# Control_Sense_TOPMOS.net
KiCad netlist of a schematic drawn in Altium Designer
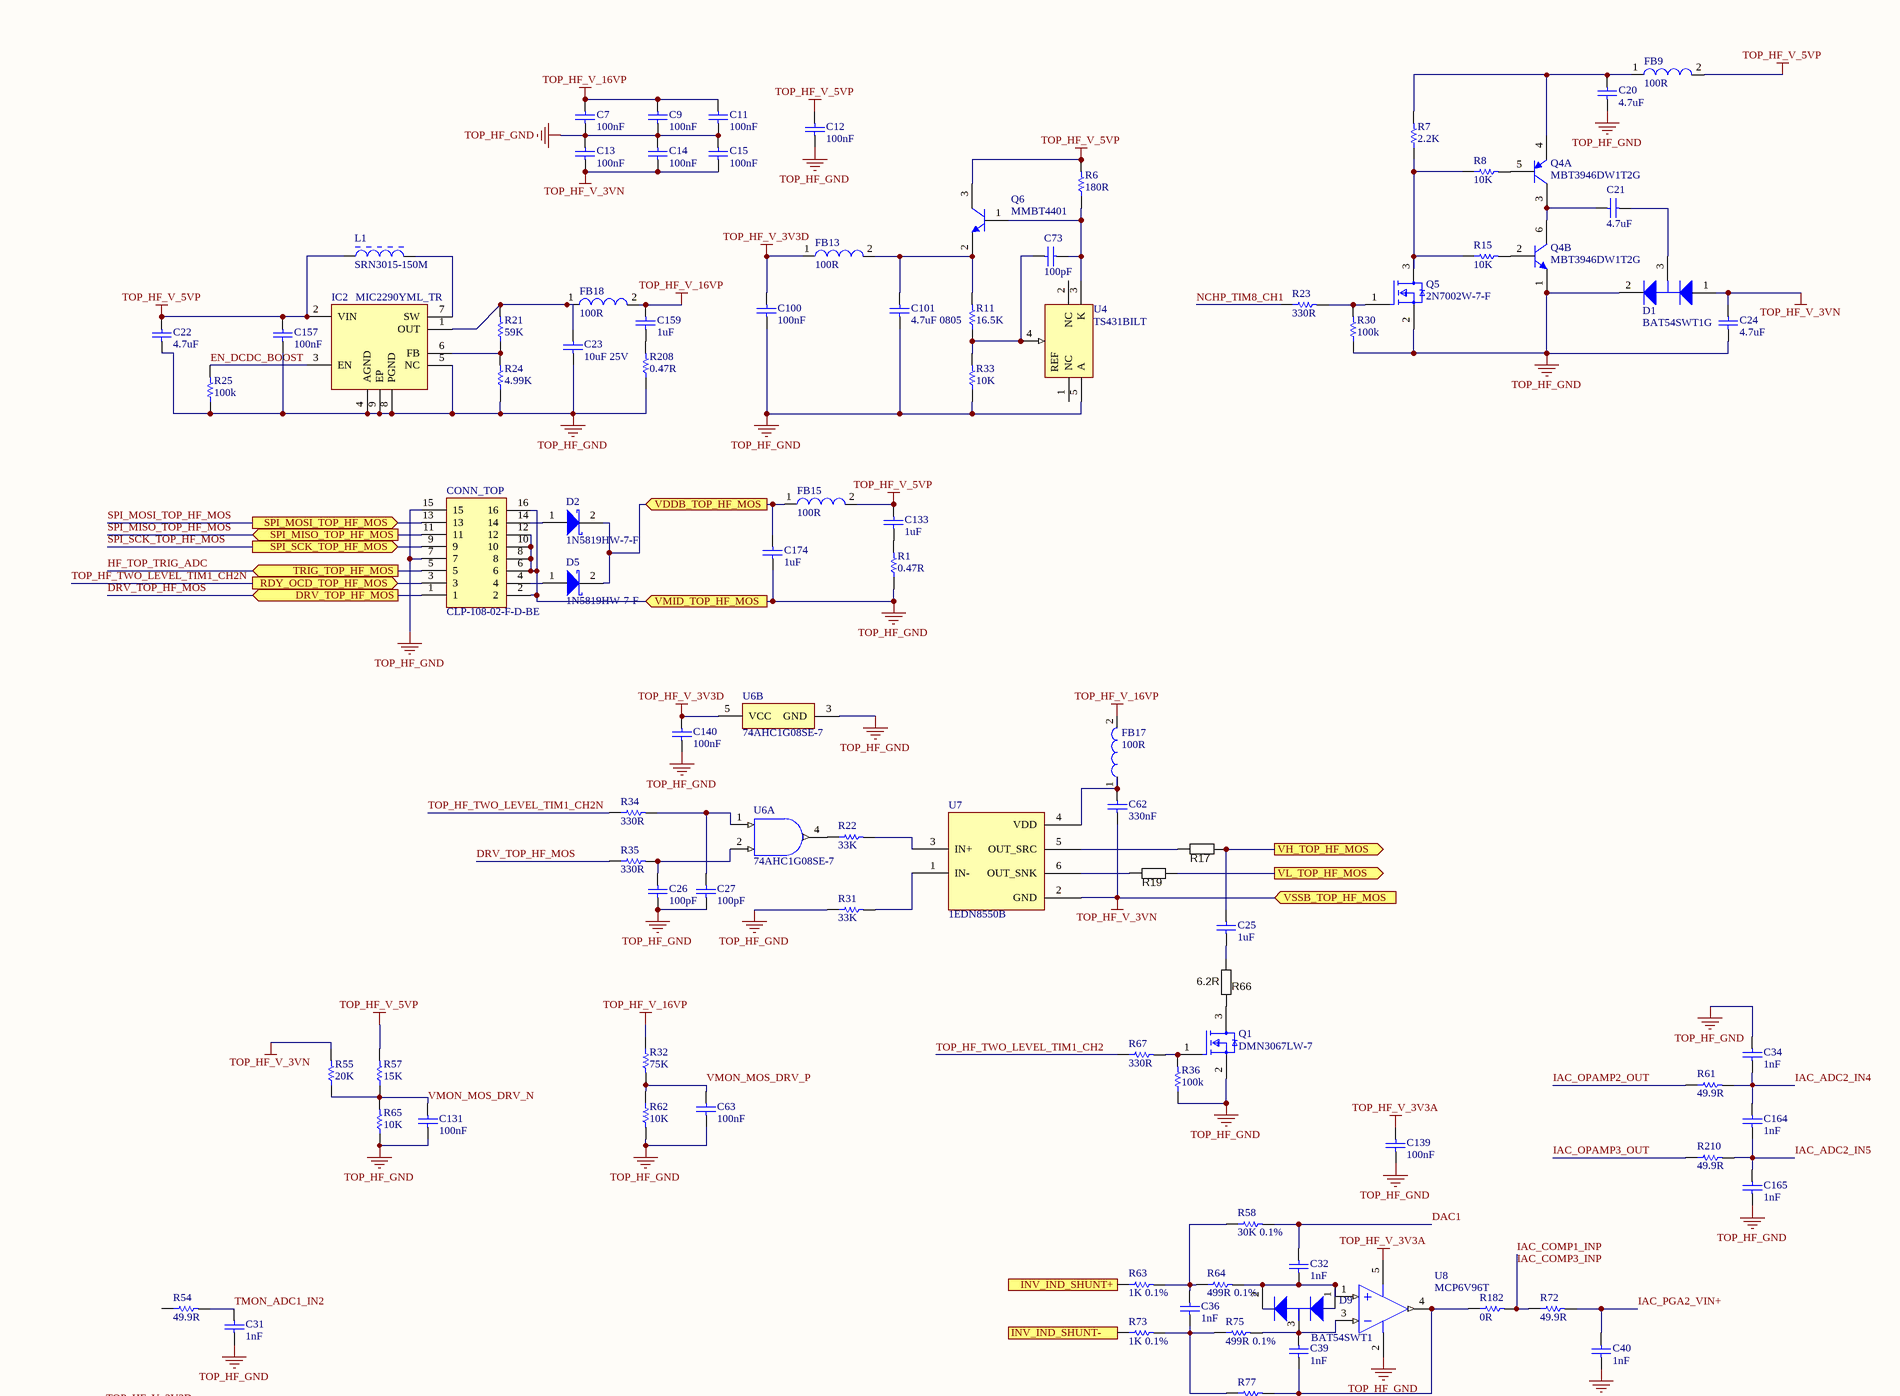
[diagram p0: Control_Sense_TOPMOS.SchDoc, top]
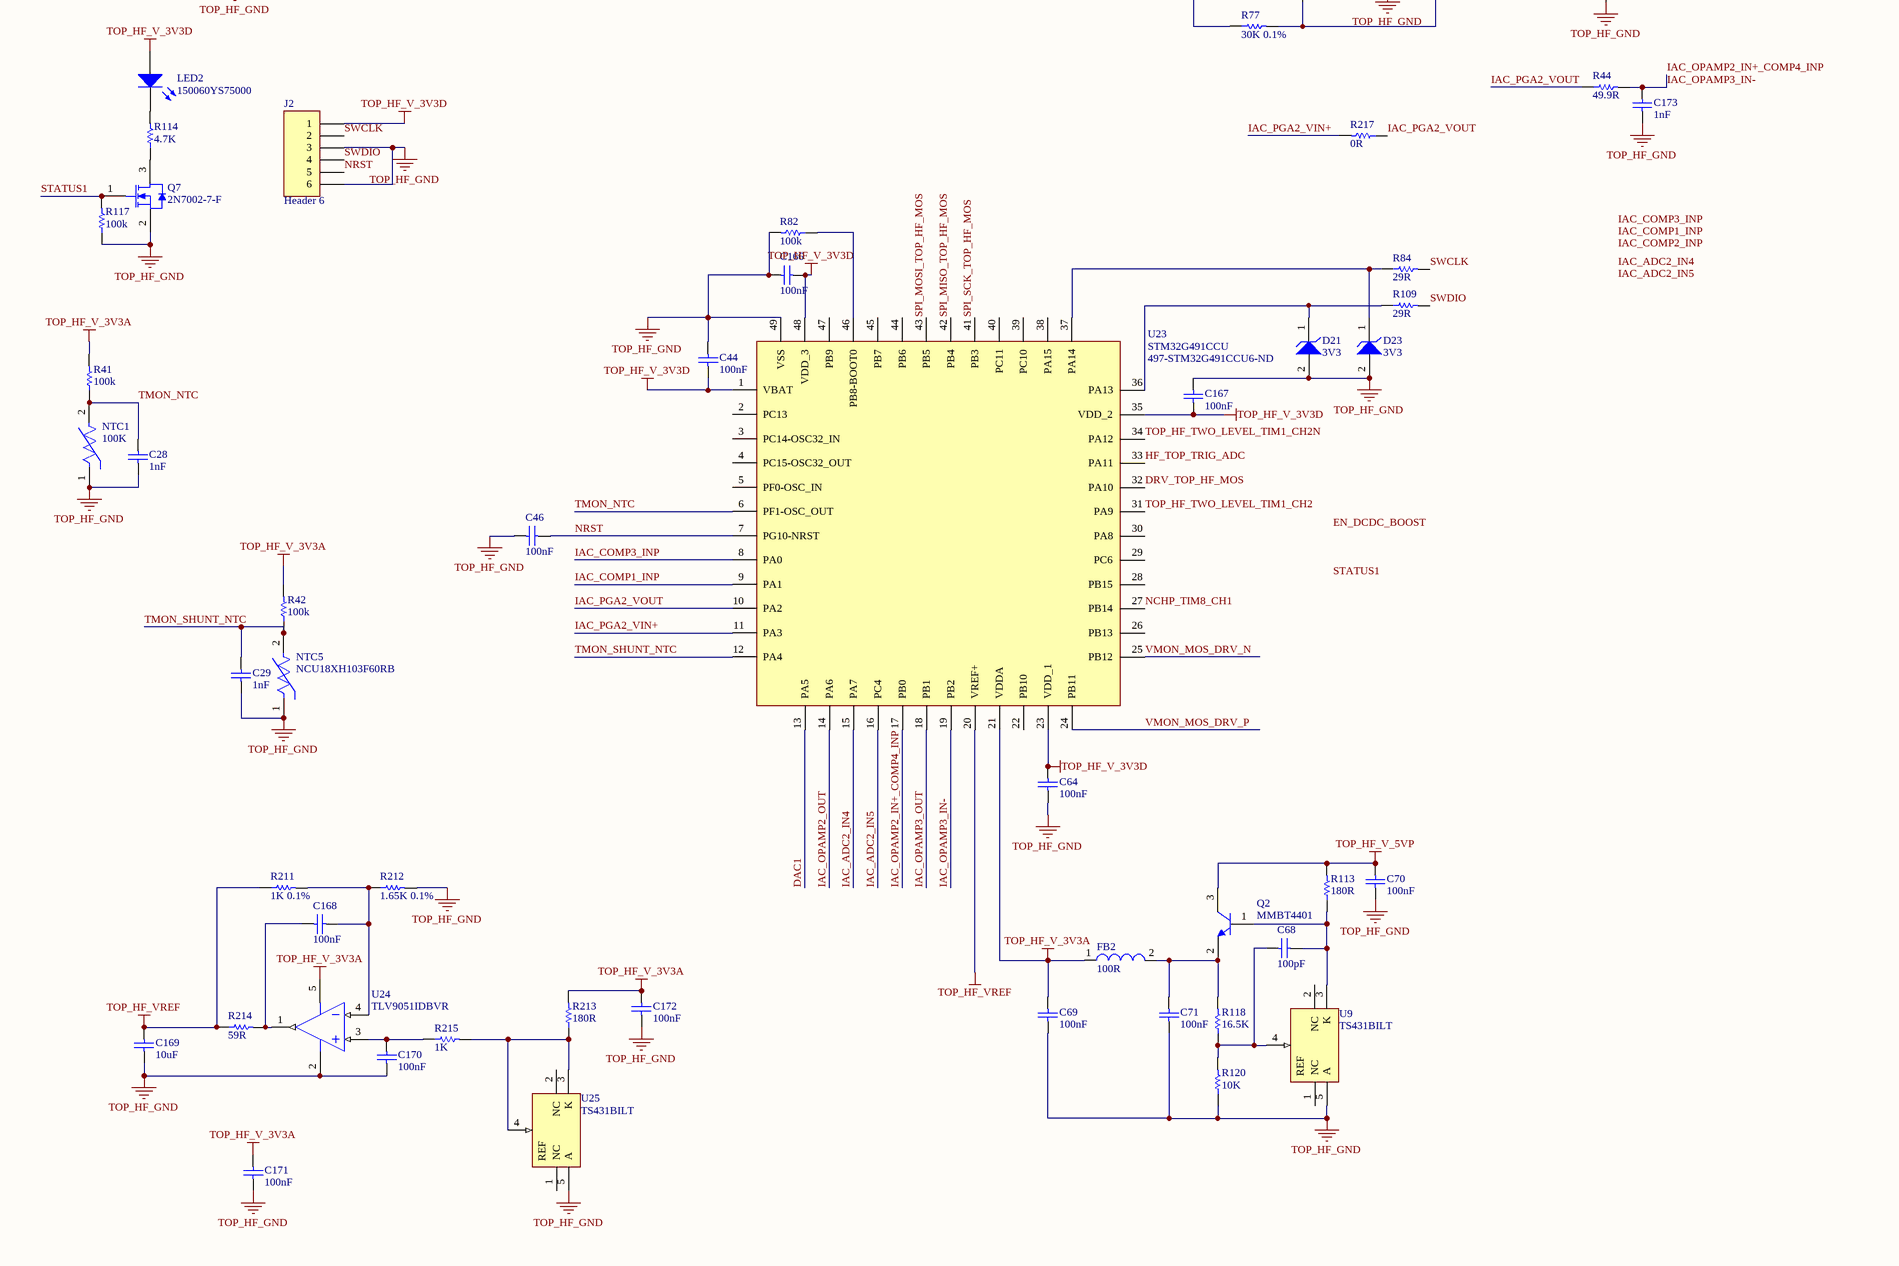
[diagram p1: Control_Sense_TOPMOS.SchDoc, bottom]

(export (version "E")
  (design (tool "Eeschema 10.0.6"))
  (components
    (comp (ref "C7")
      (value "100nF")
      (footprint "CAPC1608X90X35ML15T15")
      (fields
        (field (name "MANUFACTURER") "AVX Interconnect / Elco")
        (field (name "PART NUMBER") "06035A151JAT2A.")
        (field (name "MANUFACTURER PART NUMBER") "06035A151JAT2A")
      )
      (libsource (lib "Altium Content Vault") (part "CAP"))
    )
    (comp (ref "C9")
      (value "100nF")
      (footprint "CAPC1608X90X35ML15T15")
      (fields
        (field (name "MANUFACTURER") "AVX Interconnect / Elco")
        (field (name "PART NUMBER") "06035A151JAT2A.")
        (field (name "MANUFACTURER PART NUMBER") "06035A151JAT2A")
      )
      (libsource (lib "Altium Content Vault") (part "CAP"))
    )
    (comp (ref "C11")
      (value "100nF")
      (footprint "CAPC1608X90X35NL15T15")
      (fields
        (field (name "MANUFACTURER") "AVX Interconnect / Elco")
        (field (name "PART NUMBER") "06035A151JAT2A.")
        (field (name "MANUFACTURER PART NUMBER") "06035A151JAT2A")
      )
      (libsource (lib "Altium Content Vault") (part "CAP"))
    )
    (comp (ref "C12")
      (value "100nF")
      (footprint "CAPC1608X90X35NL15T15")
      (fields
        (field (name "MANUFACTURER") "AVX Interconnect / Elco")
        (field (name "PART NUMBER") "06035A151JAT2A.")
        (field (name "MANUFACTURER PART NUMBER") "06035A151JAT2A")
      )
      (libsource (lib "Altium Content Vault") (part "CAP"))
    )
    (comp (ref "C13")
      (value "100nF")
      (footprint "CAPC1608X90X35ML15T15")
      (fields
        (field (name "MANUFACTURER") "AVX Interconnect / Elco")
        (field (name "PART NUMBER") "06035A151JAT2A.")
        (field (name "MANUFACTURER PART NUMBER") "06035A151JAT2A")
      )
      (libsource (lib "Altium Content Vault") (part "CAP"))
    )
    (comp (ref "C14")
      (value "100nF")
      (footprint "CAPC1608X90X35ML15T15")
      (fields
        (field (name "MANUFACTURER") "AVX Interconnect / Elco")
        (field (name "PART NUMBER") "06035A151JAT2A.")
        (field (name "MANUFACTURER PART NUMBER") "06035A151JAT2A")
      )
      (libsource (lib "Altium Content Vault") (part "CAP"))
    )
    (comp (ref "C15")
      (value "100nF")
      (footprint "CAPC1608X90X35NL15T15")
      (fields
        (field (name "MANUFACTURER") "AVX Interconnect / Elco")
        (field (name "PART NUMBER") "06035A151JAT2A.")
        (field (name "MANUFACTURER PART NUMBER") "06035A151JAT2A")
      )
      (libsource (lib "Altium Content Vault") (part "CAP"))
    )
    (comp (ref "C20")
      (value "4.7uF")
      (footprint "SAMS-C0603-2_L")
      (description "Cap Ceramic 0.1uF 50VDC X7R 10% SMD 0603 Paper T/R")
      (fields
        (field (name "MANUFACTURER") "Samsung Electro-Mechanics")
        (field (name "MANUFACTURER PART NUMBER") "CL10B104KB8NNNC")
      )
      (libsource (lib "Altium Content Vault") (part "CAP-NP-2"))
    )
    (comp (ref "C21")
      (value "4.7uF")
      (footprint "SAMS-C0603-2_L")
      (description "Cap Ceramic 0.1uF 50VDC X7R 10% SMD 0603 Paper T/R")
      (fields
        (field (name "MANUFACTURER") "Samsung Electro-Mechanics")
        (field (name "MANUFACTURER PART NUMBER") "CL10B104KB8NNNC")
      )
      (libsource (lib "Altium Content Vault") (part "CAP-NP-2"))
    )
    (comp (ref "C22")
      (value "4.7uF")
      (footprint "CAPC2013X145X20NL20")
      (description "Chip Capacitor, 4.7 uF, +/- 10%, 25 V, -55 to 125 degC, 0805 (2012 Metric), RoHS, Tape and Reel")
      (fields (field (name "MANUFACTURER") "TDK") (field (name "TOLERANCE") "±10%"))
      (libsource (lib "Altium Content Vault") (part "CAP-NP-2"))
    )
    (comp (ref "C23")
      (value "10uF 25V")
      (footprint "CAPC3216X229X50LL20T25")
      (description "Chip Capacitor, 10 uF, +/- 10%, 25 V, -55 to 85 degC, 1206 (3216 Metric), RoHS, Tape and Reel")
      (fields (field (name "MANUFACTURER") "AVX"))
      (libsource (lib "Altium Content Vault") (part "CAP-NP-2"))
    )
    (comp (ref "C24")
      (value "4.7uF")
      (footprint "SAMS-C0603-2_L")
      (description "Cap Ceramic 4.7uF 6.3VDC X5R 10% SMD 0603 Paper T/R")
      (fields
        (field (name "MANUFACTURER") "Samsung Electro-Mechanics")
        (field (name "MANUFACTURER PART NUMBER") "CL10B104KB8NNNC")
      )
      (libsource (lib "Altium Content Vault") (part "CAP-NP-2"))
    )
    (comp (ref "C25")
      (value "1uF")
      (footprint "CAPC2013X135X45ML10T25")
      (description "Chip Capacitor, 0.1 uF, +/- 10%, 50 V, -55 to 125 degC, 0805 (2012 Metric), RoHS, Tape and Reel")
      (fields (field (name "VOLTAGE") "50V") (field (name "TOLERANCE") "10%"))
      (libsource (lib "Altium Content Vault") (part "CAP-NP-2"))
    )
    (comp (ref "C26")
      (value "100pF")
      (footprint "CAPC1608X90X35NL10T15")
      (fields
        (field (name "PART NUMBER") "GRM1885C1H101JA01D")
        (field (name "MANUFACTURER") "Murata")
        (field (name "TOLERANCE") "5%")
      )
      (libsource (lib "Altium Content Vault") (part "CAP"))
    )
    (comp (ref "C27")
      (value "100pF")
      (footprint "CAPC1608X90X35NL10T15")
      (fields
        (field (name "PART NUMBER") "GRM1885C1H101JA01D")
        (field (name "MANUFACTURER") "Murata")
        (field (name "TOLERANCE") "5%")
      )
      (libsource (lib "Altium Content Vault") (part "CAP"))
    )
    (comp (ref "C28")
      (value "1nF")
      (footprint "CAPC1005X56X25NL10T15")
      (fields
        (field (name "MANUFACTURER") "AVX Interconnect / Elco")
        (field (name "PART NUMBER") "04025C102MAT2A")
        (field (name "TOLERANCE") "20%")
      )
      (libsource (lib "Altium Content Vault") (part "CAP"))
    )
    (comp (ref "C29")
      (value "1nF")
      (footprint "CAPC1005X56X25NL10T15")
      (fields
        (field (name "MANUFACTURER") "AVX Interconnect / Elco")
        (field (name "PART NUMBER") "04025C102MAT2A")
        (field (name "TOLERANCE") "20%")
      )
      (libsource (lib "Altium Content Vault") (part "CAP"))
    )
    (comp (ref "C31")
      (value "1nF")
      (footprint "CAPC1005X56X25LL10T15")
      (fields
        (field (name "MANUFACTURER") "AVX Interconnect / Elco")
        (field (name "PART NUMBER") "04025C102MAT2A")
        (field (name "TOLERANCE") "20%")
      )
      (libsource (lib "Altium Content Vault") (part "CAP"))
    )
    (comp (ref "C32")
      (value "1nF")
      (footprint "CAPC1608X90X35NL15T15")
      (fields
        (field (name "MANUFACTURER") "AVX Interconnect / Elco")
        (field (name "PART NUMBER") "06035A151JAT2A.")
        (field (name "MANUFACTURER PART NUMBER") "06035A151JAT2A")
      )
      (libsource (lib "Altium Content Vault") (part "CAP"))
    )
    (comp (ref "C34")
      (value "1nF")
      (footprint "CAPC1005X56X25LL10T15")
      (fields
        (field (name "MANUFACTURER") "AVX Interconnect / Elco")
        (field (name "PART NUMBER") "04025C102MAT2A")
        (field (name "TOLERANCE") "20%")
      )
      (libsource (lib "Altium Content Vault") (part "CAP"))
    )
    (comp (ref "C36")
      (value "1nF")
      (footprint "CAPC1608X90X35LL15T15")
      (fields
        (field (name "MANUFACTURER") "AVX Interconnect / Elco")
        (field (name "PART NUMBER") "06035A151JAT2A.")
        (field (name "MANUFACTURER PART NUMBER") "06035A151JAT2A")
      )
      (libsource (lib "Altium Content Vault") (part "CAP"))
    )
    (comp (ref "C39")
      (value "1nF")
      (footprint "CAPC1608X90X35NL15T15")
      (fields
        (field (name "MANUFACTURER") "AVX Interconnect / Elco")
        (field (name "PART NUMBER") "06035A151JAT2A.")
        (field (name "MANUFACTURER PART NUMBER") "06035A151JAT2A")
      )
      (libsource (lib "Altium Content Vault") (part "CAP"))
    )
    (comp (ref "C40")
      (value "1nF")
      (footprint "CAPC1005X56X25LL10T15")
      (fields
        (field (name "MANUFACTURER") "AVX Interconnect / Elco")
        (field (name "PART NUMBER") "04025C102MAT2A")
        (field (name "TOLERANCE") "20%")
      )
      (libsource (lib "Altium Content Vault") (part "CAP"))
    )
    (comp (ref "C44")
      (value "100nF")
      (footprint "SAMS-C0603-2_N")
      (description "Cap Ceramic 0.1uF 50VDC X7R 10% SMD 0603 Paper T/R")
      (fields
        (field (name "MANUFACTURER") "Samsung Electro-Mechanics")
        (field (name "MANUFACTURER PART NUMBER") "CL10B104KB8NNNC")
      )
      (libsource (lib "Altium Content Vault") (part "CAP-NP-2"))
    )
    (comp (ref "C46")
      (value "100nF")
      (footprint "CAPC1005X56X25NL10T15")
      (fields
        (field (name "PART NUMBER") "0402YD104KAT2A")
        (field (name "MANUFACTURER") "AVX Interconnect / Elco")
        (field (name "TOLERANCE") "10%")
      )
      (libsource (lib "Altium Content Vault") (part "CAP"))
    )
    (comp (ref "C62")
      (value "330nF")
      (footprint "CAPC2013X135X45NL10T25")
      (description "Chip Capacitor, 0.1 uF, +/- 10%, 50 V, -55 to 125 degC, 0805 (2012 Metric), RoHS, Tape and Reel")
      (fields (field (name "VOLTAGE") "50V") (field (name "TOLERANCE") "10%"))
      (libsource (lib "Altium Content Vault") (part "CAP-NP-2"))
    )
    (comp (ref "C63")
      (value "100nF")
      (footprint "CAPC1005X56X25NL10T15")
      (fields
        (field (name "MANUFACTURER") "AVX Interconnect / Elco")
        (field (name "PART NUMBER") "04026D104KAT2A")
        (field (name "TOLERANCE") "10%")
      )
      (libsource (lib "Altium Content Vault") (part "CAP"))
    )
    (comp (ref "C64")
      (value "100nF")
      (footprint "SAMS-C0603-2_N")
      (description "Cap Ceramic 0.1uF 50VDC X7R 10% SMD 0603 Paper T/R")
      (fields
        (field (name "MANUFACTURER") "Samsung Electro-Mechanics")
        (field (name "MANUFACTURER PART NUMBER") "CL10B104KB8NNNC")
      )
      (libsource (lib "Altium Content Vault") (part "CAP-NP-2"))
    )
    (comp (ref "C68")
      (value "100pF")
      (footprint "CAPC1608X90X35NL10T15")
      (description "0603 100pF 50V ±5 % Tolerance C0G SMT Multilayer Ceramic Capacitor")
      (fields (field (name "PART NUMBER") "GRM1885C1H101JA01D") (field (name "MANUFACTURER") "Murata"))
      (libsource (lib "Altium Content Vault") (part "CAP"))
    )
    (comp (ref "C69")
      (value "100nF")
      (footprint "SAMS-C0603-2_L")
      (description "Cap Ceramic 0.1uF 50VDC X7R 10% SMD 0603 Paper T/R")
      (fields
        (field (name "MANUFACTURER") "Samsung Electro-Mechanics")
        (field (name "MANUFACTURER PART NUMBER") "CL10B104KB8NNNC")
      )
      (libsource (lib "Altium Content Vault") (part "CAP-NP-2"))
    )
    (comp (ref "C70")
      (value "100nF")
      (footprint "SAMS-C0603-2_N")
      (description "Cap Ceramic 0.1uF 50VDC X7R 10% SMD 0603 Paper T/R")
      (fields
        (field (name "MANUFACTURER") "Samsung Electro-Mechanics")
        (field (name "MANUFACTURER PART NUMBER") "CL10B104KB8NNNC")
      )
      (libsource (lib "Altium Content Vault") (part "CAP-NP-2"))
    )
    (comp (ref "C71")
      (value "100nF")
      (footprint "SAMS-C0603-2_N")
      (description "Cap Ceramic 0.1uF 50VDC X7R 10% SMD 0603 Paper T/R")
      (fields
        (field (name "MANUFACTURER") "Samsung Electro-Mechanics")
        (field (name "MANUFACTURER PART NUMBER") "CL10B104KB8NNNC")
      )
      (libsource (lib "Altium Content Vault") (part "CAP-NP-2"))
    )
    (comp (ref "C73")
      (value "100pF")
      (footprint "CAPC1608X90X35NL10T15")
      (description "0603 100pF 50V ±5 % Tolerance C0G SMT Multilayer Ceramic Capacitor")
      (fields (field (name "PART NUMBER") "GRM1885C1H101JA01D") (field (name "MANUFACTURER") "Murata"))
      (libsource (lib "Altium Content Vault") (part "CAP"))
    )
    (comp (ref "C100")
      (value "100nF")
      (footprint "SAMS-C0603-2_N")
      (description "Cap Ceramic 0.1uF 50VDC X7R 10% SMD 0603 Paper T/R")
      (fields
        (field (name "MANUFACTURER") "Samsung Electro-Mechanics")
        (field (name "MANUFACTURER PART NUMBER") "CL10B104KB8NNNC")
      )
      (libsource (lib "Altium Content Vault") (part "CAP-NP-2"))
    )
    (comp (ref "C101")
      (value "4.7uF 0805")
      (footprint "CAPC2013X145X20NL20")
      (description "Chip Capacitor, 4.7 uF, +/- 10%, 25 V, -55 to 125 degC, 0805 (2012 Metric), RoHS, Tape and Reel")
      (fields (field (name "MANUFACTURER") "TDK") (field (name "TOLERANCE") "±10%"))
      (libsource (lib "Altium Content Vault") (part "CAP-NP-2"))
    )
    (comp (ref "C131")
      (value "100nF")
      (footprint "CAPC1005X56X25NL10T15")
      (fields
        (field (name "MANUFACTURER") "AVX Interconnect / Elco")
        (field (name "PART NUMBER") "04026D104KAT2A")
        (field (name "TOLERANCE") "10%")
      )
      (libsource (lib "Altium Content Vault") (part "CAP"))
    )
    (comp (ref "C133")
      (value "1uF")
      (footprint "CAPC2013X140X50LL20T25")
      (description "SMD Multilayer Ceramic Capacitor, 1 µF, 25 V, 0805 [2012 Metric], ± 10%, X7R")
      (fields (field (name "PART NUMBER") "C0805C105K3RACTU") (field (name "MANUFACTURER") "Kemet"))
      (libsource (lib "Altium Content Vault") (part "CAP"))
    )
    (comp (ref "C139")
      (value "100nF")
      (footprint "SAMS-C0603-2_N")
      (description "Cap Ceramic 0.1uF 50VDC X7R 10% SMD 0603 Paper T/R")
      (fields
        (field (name "MANUFACTURER") "Samsung Electro-Mechanics")
        (field (name "MANUFACTURER PART NUMBER") "CL10B104KB8NNNC")
      )
      (libsource (lib "Altium Content Vault") (part "CAP-NP-2"))
    )
    (comp (ref "C140")
      (value "100nF")
      (footprint "CAPC1608X90X35LL15T15")
      (fields
        (field (name "MANUFACTURER") "AVX Interconnect / Elco")
        (field (name "PART NUMBER") "06035A151JAT2A.")
        (field (name "MANUFACTURER PART NUMBER") "06035A151JAT2A")
      )
      (libsource (lib "Altium Content Vault") (part "CAP"))
    )
    (comp (ref "C157")
      (value "100nF")
      (footprint "CAPC1608X90X35LL15T15")
      (fields
        (field (name "MANUFACTURER") "AVX Interconnect / Elco")
        (field (name "PART NUMBER") "06035A151JAT2A.")
        (field (name "MANUFACTURER PART NUMBER") "06035A151JAT2A")
      )
      (libsource (lib "Altium Content Vault") (part "CAP"))
    )
    (comp (ref "C159")
      (value "1uF")
      (footprint "CAPC2013X140X50LL20T25")
      (description "SMD Multilayer Ceramic Capacitor, 1 µF, 25 V, 0805 [2012 Metric], ± 10%, X7R")
      (fields (field (name "PART NUMBER") "C0805C105K3RACTU") (field (name "MANUFACTURER") "Kemet"))
      (libsource (lib "Altium Content Vault") (part "CAP"))
    )
    (comp (ref "C164")
      (value "1nF")
      (footprint "CAPC1005X56X25LL10T15")
      (fields
        (field (name "MANUFACTURER") "AVX Interconnect / Elco")
        (field (name "PART NUMBER") "04025C102MAT2A")
        (field (name "TOLERANCE") "20%")
      )
      (libsource (lib "Altium Content Vault") (part "CAP"))
    )
    (comp (ref "C165")
      (value "1nF")
      (footprint "CAPC1005X56X25LL10T15")
      (fields
        (field (name "MANUFACTURER") "AVX Interconnect / Elco")
        (field (name "PART NUMBER") "04025C102MAT2A")
        (field (name "TOLERANCE") "20%")
      )
      (libsource (lib "Altium Content Vault") (part "CAP"))
    )
    (comp (ref "C166")
      (value "100nF")
      (footprint "SAMS-C0603-2_N")
      (description "Cap Ceramic 0.1uF 50VDC X7R 10% SMD 0603 Paper T/R")
      (fields
        (field (name "MANUFACTURER") "Samsung Electro-Mechanics")
        (field (name "MANUFACTURER PART NUMBER") "CL10B104KB8NNNC")
      )
      (libsource (lib "Altium Content Vault") (part "CAP-NP-2"))
    )
    (comp (ref "C167")
      (value "100nF")
      (footprint "SAMS-C0603-2_N")
      (description "Cap Ceramic 0.1uF 50VDC X7R 10% SMD 0603 Paper T/R")
      (fields
        (field (name "MANUFACTURER") "Samsung Electro-Mechanics")
        (field (name "MANUFACTURER PART NUMBER") "CL10B104KB8NNNC")
      )
      (libsource (lib "Altium Content Vault") (part "CAP-NP-2"))
    )
    (comp (ref "C168")
      (value "100nF")
      (footprint "SAMS-C0603-2_L")
      (description "Cap Ceramic 0.1uF 50VDC X7R 10% SMD 0603 Paper T/R")
      (fields
        (field (name "MANUFACTURER") "Samsung Electro-Mechanics")
        (field (name "MANUFACTURER PART NUMBER") "CL10B104KB8NNNC")
      )
      (libsource (lib "Altium Content Vault") (part "CAP-NP-2"))
    )
    (comp (ref "C169")
      (value "10uF")
      (footprint "CAPC1608X90X35LL15T15")
      (fields
        (field (name "MANUFACTURER") "AVX Interconnect / Elco")
        (field (name "PART NUMBER") "06036D106MAT2A")
      )
      (libsource (lib "Altium Content Vault") (part "CAP"))
    )
    (comp (ref "C170")
      (value "100nF")
      (footprint "SAMS-C0603-2_L")
      (description "Cap Ceramic 0.1uF 50VDC X7R 10% SMD 0603 Paper T/R")
      (fields
        (field (name "MANUFACTURER") "Samsung Electro-Mechanics")
        (field (name "MANUFACTURER PART NUMBER") "CL10B104KB8NNNC")
      )
      (libsource (lib "Altium Content Vault") (part "CAP-NP-2"))
    )
    (comp (ref "C171")
      (value "100nF")
      (footprint "SAMS-C0603-2_L")
      (description "Cap Ceramic 0.1uF 50VDC X7R 10% SMD 0603 Paper T/R")
      (fields
        (field (name "MANUFACTURER") "Samsung Electro-Mechanics")
        (field (name "MANUFACTURER PART NUMBER") "CL10B104KB8NNNC")
      )
      (libsource (lib "Altium Content Vault") (part "CAP-NP-2"))
    )
    (comp (ref "C172")
      (value "100nF")
      (footprint "SAMS-C0603-2_N")
      (description "Cap Ceramic 0.1uF 50VDC X7R 10% SMD 0603 Paper T/R")
      (fields
        (field (name "MANUFACTURER") "Samsung Electro-Mechanics")
        (field (name "MANUFACTURER PART NUMBER") "CL10B104KB8NNNC")
      )
      (libsource (lib "Altium Content Vault") (part "CAP-NP-2"))
    )
    (comp (ref "C173")
      (value "1nF")
      (footprint "CAPC1005X56X25LL10T15")
      (fields
        (field (name "MANUFACTURER") "AVX Interconnect / Elco")
        (field (name "PART NUMBER") "04025C102MAT2A")
        (field (name "TOLERANCE") "20%")
      )
      (libsource (lib "Altium Content Vault") (part "CAP"))
    )
    (comp (ref "C174")
      (value "1uF")
      (footprint "CAPC2013X140X50LL20T25")
      (description "SMD Multilayer Ceramic Capacitor, 1 µF, 25 V, 0805 [2012 Metric], ± 10%, X7R")
      (fields (field (name "PART NUMBER") "C0805C105K3RACTU") (field (name "MANUFACTURER") "Kemet"))
      (libsource (lib "Altium Content Vault") (part "CAP"))
    )
    (comp (ref "CONN_TOP")
      (value "CLP-108-02-F-D-BE")
      (footprint "SamacSys:CLP-108-02-XXX-D-BE")
      (description "Connector")
      (fields (field (name "MOUSER PART NUMBER") "200-CLP10802FDBE"))
      (libsource (lib "*") (part "CLP-108-02-F-D-BE"))
    )
    (comp (ref "D1")
      (value "BAT54SWT1G")
      (footprint "ONSC-SOT-323-3-419-04_V")
      (description "Dual Series Schottky Barrier Diodes, 3-Pin SOT-323, Pb-Free, Tape and Reel")
      (fields (field (name "MANUFACTURER") "On Semiconductor"))
      (libsource (lib "") (part "ONSC-D-A1K2C3-3_1"))
    )
    (comp (ref "D2")
      (value "1N5819HW-7-F")
      (footprint "DIOD-SOD-123-2_V")
      (fields (field (name "MANUFACTURER") "Diodes Inc"))
      (libsource (lib "Altium Content Vault") (part "DIOD-DSKY-A1K2-2"))
    )
    (comp (ref "D5")
      (value "1N5819HW-7-F")
      (footprint "DIOD-SOD-123-2_V")
      (fields (field (name "MANUFACTURER") "Diodes Inc"))
      (libsource (lib "Altium Content Vault") (part "DIOD-DSKY-A1K2-2"))
    )
    (comp (ref "D9")
      (value "BAT54SWT1")
      (footprint "ONSC-SOT-323-3-419-04_V")
      (description "Dual Series Schottky Barrier Diodes, 3-Pin SOT-323, Tape and Reel")
      (fields (field (name "MANUFACTURER") "On Semiconductor"))
      (libsource (lib "Altium Content Vault") (part "ONSC-D-A1K2C3-3"))
    )
    (comp (ref "D21")
      (value "3V3")
      (footprint "ONSC-SOD-523-2-502-01_V")
      (fields (field (name "MANUFACTURER") "On Semiconductor") (field (name "PARTNUMBER") "ESD5Z3.3T1G"))
      (libsource (lib "Altium Content Vault") (part "ONSC-K1A2-2"))
    )
    (comp (ref "D23")
      (value "3V3")
      (footprint "ONSC-SOD-523-2-502-01_V")
      (fields (field (name "MANUFACTURER") "On Semiconductor") (field (name "PARTNUMBER") "ESD5Z3.3T1G"))
      (libsource (lib "Altium Content Vault") (part "ONSC-K1A2-2"))
    )
    (comp (ref "FB2")
      (value "100R")
      (footprint "SMD-0603")
      (description "SMD EMI Suppression Ferrite Bead WE-CBF, Z = 1500 Ohm")
      (libsource (lib "Altium Content Vault") (part "PAS-IND-INDUCTOR-2"))
    )
    (comp (ref "FB9")
      (value "100R")
      (footprint "SMD-0603")
      (description "SMD EMI Suppression Ferrite Bead WE-CBF, Z = 1500 Ohm")
      (libsource (lib "Altium Content Vault") (part "PAS-IND-INDUCTOR-2"))
    )
    (comp (ref "FB13")
      (value "100R")
      (footprint "SMD-0603")
      (description "SMD EMI Suppression Ferrite Bead WE-CBF, Z = 1500 Ohm")
      (libsource (lib "Altium Content Vault") (part "PAS-IND-INDUCTOR-2"))
    )
    (comp (ref "FB15")
      (value "100R")
      (footprint "SMD-0603")
      (description "SMD EMI Suppression Ferrite Bead WE-CBF, Z = 1500 Ohm")
      (libsource (lib "Altium Content Vault") (part "PAS-IND-INDUCTOR-2"))
    )
    (comp (ref "FB17")
      (value "100R")
      (footprint "SMD-0603")
      (description "SMD EMI Suppression Ferrite Bead WE-CBF, Z = 1500 Ohm")
      (libsource (lib "Altium Content Vault") (part "PAS-IND-INDUCTOR-2"))
    )
    (comp (ref "FB18")
      (value "100R")
      (footprint "SMD-0603")
      (description "SMD EMI Suppression Ferrite Bead WE-CBF, Z = 1500 Ohm")
      (libsource (lib "Altium Content Vault") (part "PAS-IND-INDUCTOR-2"))
    )
    (comp (ref "IC2")
      (value "MIC2290YML_TR")
      (footprint "SamacSys:SON50P200X200X95-9N-D")
      (description "Integrated Circuit")
      (fields (field (name "MANUFACTURER_PART_NUMBER") "MIC2290YML TR"))
      (libsource (lib "*") (part "MIC2290YML_TR"))
    )
    (comp (ref "J2")
      (value "Header 6")
      (footprint "HDR1X6")
      (description "Header, 6-Pin")
      (fields (field (name "PUBLISHER") "Altium Limited"))
      (libsource (lib "Miscellaneous Connectors") (part "Header 6"))
    )
    (comp (ref "L1")
      (value "SRN3015-150M")
      (footprint "BOUR-SRN3015-2_V")
      (fields (field (name "MANUFACTURER") "Bourns") (field (name "TOLERANCE") "20%"))
      (libsource (lib "Altium Content Vault") (part "BOUR-IND-2A"))
    )
    (comp (ref "LED2")
      (value "150060YS75000")
      (footprint "0603_A")
      (description "SMD mono-color Chip LED, WL-SMCW, Yellow")
      (fields (field (name "MANUFACTURER") "Wuerth Elektronik"))
      (libsource (lib "Altium Content Vault") (part "WE-LED_K1A2-2"))
    )
    (comp (ref "NTC1")
      (value "100K")
      (footprint "FP-NXR_151B030-MFG")
      (description "Thermistor NTC 10kΩ ±1% 2-Pin Radial Bulk")
      (fields (field (name "TOLERANCE") "1%"))
      (libsource (lib "Altium Content Vault") (part "3b148a6ebabc5fb4d708a66c052d352"))
    )
    (comp (ref "NTC5")
      (value "NCU18XH103F60RB")
      (footprint "FP-NCU18-0_15-MFG")
      (description "THERMISTOR NTC")
      (libsource (lib "Altium Content Vault") (part "3b148a6ebabc5fb4d708a66c052d352"))
    )
    (comp (ref "Q1")
      (value "DMN3067LW-7")
      (footprint "FP-SOT323-IPC_C")
      (description "MOSFET N-CH 60V 115MA SOT323")
      (libsource (lib "Altium Content Vault") (part "381a366367e4312d0f7d2747150cb42"))
    )
    (comp (ref "Q2")
      (value "MMBT4401")
      (footprint "SOT23-3")
      (description "NPN General-Purpose Amplifier, 0.6 A, 40 V, -55 to 150 degC, 3-Pin SOT-23, RoHS, Tape and Reel")
      (fields (field (name "MANUFACTURER") "FairchildSemiconductor"))
      (libsource (lib "PBL - Transistors") (part "BJT-NPN-BEC-3"))
    )
    (comp (ref "Q4")
      (value "MBT3946DW1T2G")
      (footprint "ONSC-SC70-6-419B-02_W_V")
      (description "Complementary General Purpose Transistors, 6-Pin SC70, Pb-Free, Tape and Reel")
      (fields (field (name "MANUFACTURER") "On Semiconductor"))
      (libsource (lib "Altium Content Vault") (part "ONSC-NPN_PNP-6"))
    )
    (comp (ref "Q5")
      (value "2N7002W-7-F")
      (footprint "FP-SOT323-IPC_B")
      (description "MOSFET N-CH 60V 115MA SOT323")
      (libsource (lib "Altium Content Vault") (part "381a366367e4312d0f7d2747150cb42"))
    )
    (comp (ref "Q6")
      (value "MMBT4401")
      (footprint "SOT23-3")
      (description "NPN General-Purpose Amplifier, 0.6 A, 40 V, -55 to 150 degC, 3-Pin SOT-23, RoHS, Tape and Reel")
      (fields (field (name "MANUFACTURER") "FairchildSemiconductor"))
      (libsource (lib "PBL - Transistors") (part "BJT-NPN-BEC-3"))
    )
    (comp (ref "Q7")
      (value "2N7002-7-F")
      (footprint "DIOD-SOT23-3_V")
      (fields (field (name "MANUFACTURER") "DiodesIncorporated"))
      (libsource (lib "Altium Content Vault") (part "NEMOS-GSD-3"))
    )
    (comp (ref "R1")
      (value "0.47R")
      (footprint "RESC1608X55X25ML10T15")
      (description "Chip Resistor, 0 Ohm, +/- 5%, 0.1 W, -55 to 155 degC, 0603 (1608 Metric), RoHS, Tape and Reel")
      (fields (field (name "TOLERANCE") "5%") (field (name "MANUFACTURER") "Yageo"))
      (libsource (lib "Altium Content Vault") (part "RES-2"))
    )
    (comp (ref "R6")
      (value "180R")
      (footprint "RESC1608X55X25LL10T15")
      (description "Chip Resistor, 180 Ohm, +/- 1%, 0.1 W, -55 to 155 degC, 0603 (1608 Metric), RoHS, Tape and Reel")
      (fields (field (name "TOLERANCE") "1%") (field (name "MANUFACTURER") "Yageo"))
      (libsource (lib "Altium Content Vault") (part "RES-2"))
    )
    (comp (ref "R7")
      (value "2.2K")
      (footprint "RESC1608X55X25NL10T15")
      (fields
        (field (name "TOLERANCE") "1%")
        (field (name "MANUFACTURER") "Yageo")
        (field (name "MANUFACTURER PART NUMBER") "RC0603FR-072K2L")
      )
      (libsource (lib "Altium Content Vault") (part "RES-2"))
    )
    (comp (ref "R8")
      (value "10K")
      (footprint "RESC1608X55X30NL20T10")
      (description "RK73B1JTTD103J")
      (fields (field (name "MANUFACTURER") "KOA Speer") (field (name "TOLERANCE") "5%"))
      (libsource (lib "Altium Content Vault") (part "RES"))
    )
    (comp (ref "R11")
      (value "16.5K")
      (footprint "RESC1608X55X30NL15T15")
      (description "RES, 16K5, 1%, 0.1W, 0603, THICK FILM")
      (fields (field (name "MANUFACTURER") "Panasonic") (field (name "PART NUMBER") "ERJ-3EKF1652V"))
      (libsource (lib "Altium Content Vault") (part "RES"))
    )
    (comp (ref "R15")
      (value "10K")
      (footprint "RESC1608X55X30NL20T10")
      (description "RK73B1JTTD103J")
      (fields (field (name "MANUFACTURER") "KOA Speer") (field (name "TOLERANCE") "5%"))
      (libsource (lib "Altium Content Vault") (part "RES"))
    )
    (comp (ref "R17")
      (value "RES_EMPTY_0805")
      (footprint "RESC2012X70N")
      (description "Resistor, 0805 SMD, Empty footprint")
      (libsource (lib "PBL - Resistors") (part "RES_EMPTY_0805"))
    )
    (comp (ref "R19")
      (value "RES_EMPTY_0805")
      (footprint "RESC2012X70N")
      (description "Resistor, 0805 SMD, Empty footprint")
      (libsource (lib "PBL - Resistors") (part "RES_EMPTY_0805"))
    )
    (comp (ref "R21")
      (value "59K")
      (footprint "RESC1608X55X30NL15T15")
      (fields
        (field (name "MANUFACTURER") "Panasonic")
        (field (name "PART NUMBER") "ERJ-3EKF5902V")
        (field (name "TOLERANCE") "1%")
      )
      (libsource (lib "Altium Content Vault") (part "RES"))
    )
    (comp (ref "R22")
      (value "33K")
      (footprint "RESC1005X40X25ML05T05")
      (fields
        (field (name "PART NUMBER") "ERJ2RKF3302X")
        (field (name "MANUFACTURER") "Panasonic")
        (field (name "MANUFACTURER PART NUMBER") "ERJ-2RKF3302X")
      )
      (libsource (lib "Altium Content Vault") (part "RES"))
    )
    (comp (ref "R23")
      (value "330R")
      (footprint "RESC1608X55X25NL10T15")
      (description "Chip Resistor, 330 Ohm, +/- 1%, 0.1 W, -55 to 155 degC, 0603 (1608 Metric), RoHS, Tape and Reel")
      (fields (field (name "TOLERANCE") "10%"))
      (libsource (lib "Altium Content Vault") (part "RES-2"))
    )
    (comp (ref "R24")
      (value "4.99K")
      (footprint "RESC1609X50X30NL10T20")
      (fields
        (field (name "MANUFACTURER") "Vishay Dale")
        (field (name "PART NUMBER") "CRCW06034K99FKTA")
        (field (name "TOLERANCE") "1%")
      )
      (libsource (lib "Altium Content Vault") (part "RES"))
    )
    (comp (ref "R25")
      (value "100k")
      (footprint "RESC1608X55X30NL15T15")
      (description "Res Thick Film 0603 100K Ohm 1% 0.1W(1/10W) ±100ppm/C Pad SMD Automotive T/R")
      (fields (field (name "PART NUMBER") "ERJ-3EKF1003V") (field (name "MANUFACTURER") "Panasonic"))
      (libsource (lib "Altium Content Vault") (part "RES"))
    )
    (comp (ref "R30")
      (value "100k")
      (footprint "RESC1608X55X30NL15T15")
      (description "Res Thick Film 0603 100K Ohm 1% 0.1W(1/10W) ±100ppm/C Pad SMD Automotive T/R")
      (fields (field (name "PART NUMBER") "ERJ-3EKF1003V") (field (name "MANUFACTURER") "Panasonic"))
      (libsource (lib "Altium Content Vault") (part "RES"))
    )
    (comp (ref "R31")
      (value "33K")
      (footprint "RESC1005X40X25ML05T05")
      (fields
        (field (name "PART NUMBER") "ERJ2RKF3302X")
        (field (name "MANUFACTURER") "Panasonic")
        (field (name "MANUFACTURER PART NUMBER") "ERJ-2RKF3302X")
      )
      (libsource (lib "Altium Content Vault") (part "RES"))
    )
    (comp (ref "R32")
      (value "75K")
      (footprint "RESC1608X55X30NL15T15")
      (fields
        (field (name "PART NUMBER") "ERJ-3EKF7502V")
        (field (name "MANUFACTURER") "Panasonic")
        (field (name "TOLERANCE") "1%")
      )
      (libsource (lib "Altium Content Vault") (part "RES"))
    )
    (comp (ref "R33")
      (value "10K")
      (footprint "RESC1609X55X30LL15T15")
      (description "Chip Resistor, 10 KOhm, +/- 1%, 0.1 W, -55 to 155 degC, 0603 (1608 Metric), RoHS, Tape and Reel")
      (fields (field (name "TOLERANCE") "1%") (field (name "MANUFACTURER") "Panasonic"))
      (libsource (lib "Altium Content Vault") (part "RES-2"))
    )
    (comp (ref "R34")
      (value "330R")
      (footprint "RESC1608X55X25NL10T15")
      (description "Chip Resistor, 330 Ohm, +/- 1%, 0.1 W, -55 to 155 degC, 0603 (1608 Metric), RoHS, Tape and Reel")
      (fields (field (name "TOLERANCE") "10%"))
      (libsource (lib "Altium Content Vault") (part "RES-2"))
    )
    (comp (ref "R35")
      (value "330R")
      (footprint "RESC1608X55X25NL10T15")
      (description "Chip Resistor, 330 Ohm, +/- 1%, 0.1 W, -55 to 155 degC, 0603 (1608 Metric), RoHS, Tape and Reel")
      (fields (field (name "TOLERANCE") "10%"))
      (libsource (lib "Altium Content Vault") (part "RES-2"))
    )
    (comp (ref "R36")
      (value "100k")
      (footprint "RESC1608X55X30NL15T15")
      (description "Res Thick Film 0603 100K Ohm 1% 0.1W(1/10W) ±100ppm/C Pad SMD Automotive T/R")
      (fields (field (name "PART NUMBER") "ERJ-3EKF1003V") (field (name "MANUFACTURER") "Panasonic"))
      (libsource (lib "Altium Content Vault") (part "RES"))
    )
    (comp (ref "R41")
      (value "100k")
      (footprint "RESC1608X55X30NL15T15")
      (description "Res Thick Film 0603 100K Ohm 1% 0.1W(1/10W) ±100ppm/C Pad SMD Automotive T/R")
      (fields (field (name "PART NUMBER") "ERJ-3EKF1003V") (field (name "MANUFACTURER") "Panasonic"))
      (libsource (lib "Altium Content Vault") (part "RES"))
    )
    (comp (ref "R42")
      (value "100k")
      (footprint "RESC1608X55X30NL15T15")
      (description "Res Thick Film 0603 100K Ohm 1% 0.1W(1/10W) ±100ppm/C Pad SMD Automotive T/R")
      (fields (field (name "PART NUMBER") "ERJ-3EKF1003V") (field (name "MANUFACTURER") "Panasonic"))
      (libsource (lib "Altium Content Vault") (part "RES"))
    )
    (comp (ref "R44")
      (value "49.9R")
      (footprint "RESC1005X40X25NL05T05")
      (fields (field (name "MANUFACTURER") "Panasonic") (field (name "PART NUMBER") "ERJ-2RKF49R9X"))
      (libsource (lib "Altium Content Vault") (part "RES"))
    )
    (comp (ref "R54")
      (value "49.9R")
      (footprint "RESC1005X40X25NL05T05")
      (fields (field (name "MANUFACTURER") "Panasonic") (field (name "PART NUMBER") "ERJ-2RKF49R9X"))
      (libsource (lib "Altium Content Vault") (part "RES"))
    )
    (comp (ref "R55")
      (value "20K")
      (footprint "RESC1608X55X30NL20T10")
      (description "RK73B1JTTD103J")
      (fields (field (name "MANUFACTURER") "KOA Speer") (field (name "TOLERANCE") "5%"))
      (libsource (lib "Altium Content Vault") (part "RES"))
    )
    (comp (ref "R57")
      (value "15K")
      (footprint "RESC1608X55X30NL20T10")
      (description "RK73B1JTTD103J")
      (fields (field (name "MANUFACTURER") "KOA Speer") (field (name "TOLERANCE") "5%"))
      (libsource (lib "Altium Content Vault") (part "RES"))
    )
    (comp (ref "R58")
      (value "30K 0.1%")
      (footprint "RESC1608X55N")
      (description "Resistor, SMD 30 kOhm 0603  ±  0.1 %, ERA3AEB303V, Panasonic Automotive & Industrial Systems")
      (fields (field (name "MANUFACTURER") "Panasonic") (field (name "PART NUMBER") "ERA3AEB303V"))
      (libsource (lib "PBL - Resistors") (part "RES"))
    )
    (comp (ref "R61")
      (value "49.9R")
      (footprint "RESC1005X40X25NL05T05")
      (fields (field (name "MANUFACTURER") "Panasonic") (field (name "PART NUMBER") "ERJ-2RKF49R9X"))
      (libsource (lib "Altium Content Vault") (part "RES"))
    )
    (comp (ref "R62")
      (value "10K")
      (footprint "RESC1608X55X30NL20T10")
      (description "RK73B1JTTD103J")
      (fields (field (name "MANUFACTURER") "KOA Speer") (field (name "TOLERANCE") "5%"))
      (libsource (lib "Altium Content Vault") (part "RES"))
    )
    (comp (ref "R63")
      (value "1K 0.1%")
      (footprint "RESC1608X55X25NL10T15")
      (description "RES SMD 1K OHM 0.1% 1/10W 0603")
      (fields (field (name "PART NUMBER") "RT0603BRE071KL") (field (name "MANUFACTURER") "Yageo"))
      (libsource (lib "Altium Content Vault") (part "RES"))
    )
    (comp (ref "R64")
      (value "499R 0.1%")
      (footprint "RESC1608X55N")
      (description "Res Thin Film 0603 499 Ohm 0.1% 1/10W ±25ppm/°C Molded SMD SMD Punched Carrier T/R")
      (fields (field (name "PART NUMBER") "ERA3AEB4990V") (field (name "MANUFACTURER") "Panasonic"))
      (libsource (lib "PBL - Resistors") (part "RES"))
    )
    (comp (ref "R65")
      (value "10K")
      (footprint "RESC1608X55X30NL20T10")
      (description "RK73B1JTTD103J")
      (fields (field (name "MANUFACTURER") "KOA Speer") (field (name "TOLERANCE") "5%"))
      (libsource (lib "Altium Content Vault") (part "RES"))
    )
    (comp (ref "R66")
      (value "6.2R")
      (footprint "RESC2012X70N")
      (description "Resistor, 0805 SMD, Empty footprint")
      (libsource (lib "") (part "RES_EMPTY_0805_1"))
    )
    (comp (ref "R67")
      (value "330R")
      (footprint "RESC1608X55X25NL10T15")
      (description "Chip Resistor, 330 Ohm, +/- 1%, 0.1 W, -55 to 155 degC, 0603 (1608 Metric), RoHS, Tape and Reel")
      (fields (field (name "TOLERANCE") "10%"))
      (libsource (lib "Altium Content Vault") (part "RES-2"))
    )
    (comp (ref "R72")
      (value "49.9R")
      (footprint "RESC1005X40X25NL05T05")
      (fields (field (name "MANUFACTURER") "Panasonic") (field (name "PART NUMBER") "ERJ-2RKF49R9X"))
      (libsource (lib "Altium Content Vault") (part "RES"))
    )
    (comp (ref "R73")
      (value "1K 0.1%")
      (footprint "RESC1608X55X25NL10T15")
      (description "RES SMD 1K OHM 0.1% 1/10W 0603")
      (fields (field (name "PART NUMBER") "RT0603BRE071KL") (field (name "MANUFACTURER") "Yageo"))
      (libsource (lib "Altium Content Vault") (part "RES"))
    )
    (comp (ref "R75")
      (value "499R 0.1%")
      (footprint "RESC1608X55N")
      (description "Res Thin Film 0603 499 Ohm 0.1% 1/10W ±25ppm/°C Molded SMD SMD Punched Carrier T/R")
      (fields (field (name "PART NUMBER") "ERA3AEB4990V") (field (name "MANUFACTURER") "Panasonic"))
      (libsource (lib "PBL - Resistors") (part "RES"))
    )
    (comp (ref "R77")
      (value "30K 0.1%")
      (footprint "RESC1608X55N")
      (description "Resistor, SMD 30 kOhm 0603  ±  0.1 %, ERA3AEB303V, Panasonic Automotive & Industrial Systems")
      (fields (field (name "MANUFACTURER") "Panasonic") (field (name "PART NUMBER") "ERA3AEB303V"))
      (libsource (lib "PBL - Resistors") (part "RES"))
    )
    (comp (ref "R82")
      (value "100k")
      (footprint "RESC1608X55X30NL15T15")
      (description "Res Thick Film 0603 100K Ohm 1% 0.1W(1/10W) ±100ppm/C Pad SMD Automotive T/R")
      (fields (field (name "PART NUMBER") "ERJ-3EKF1003V") (field (name "MANUFACTURER") "Panasonic"))
      (libsource (lib "Altium Content Vault") (part "RES"))
    )
    (comp (ref "R84")
      (value "29R")
      (footprint "RESC1608X55X30NL20T10")
      (description "RK73B1JTTD103J")
      (fields (field (name "MANUFACTURER") "KOA Speer") (field (name "TOLERANCE") "5%"))
      (libsource (lib "Altium Content Vault") (part "RES"))
    )
    (comp (ref "R109")
      (value "29R")
      (footprint "RESC1608X55X30NL20T10")
      (description "RK73B1JTTD103J")
      (fields (field (name "MANUFACTURER") "KOA Speer") (field (name "TOLERANCE") "5%"))
      (libsource (lib "Altium Content Vault") (part "RES"))
    )
    (comp (ref "R113")
      (value "180R")
      (footprint "RESC1608X55X25LL10T15")
      (description "Chip Resistor, 180 Ohm, +/- 1%, 0.1 W, -55 to 155 degC, 0603 (1608 Metric), RoHS, Tape and Reel")
      (fields (field (name "TOLERANCE") "1%") (field (name "MANUFACTURER") "Yageo"))
      (libsource (lib "Altium Content Vault") (part "RES-2"))
    )
    (comp (ref "R114")
      (value "4.7K")
      (footprint "RESC1608X55X25ML10T15")
      (fields
        (field (name "MANUFACTURER") "Yageo")
        (field (name "MANUFACTURER PART NUMBER") "RC0603FR-07470RL")
        (field (name "TOLERANCE") "1%")
      )
      (libsource (lib "Altium Content Vault") (part "RES-2"))
    )
    (comp (ref "R117")
      (value "100k")
      (footprint "RESC1608X55X25ML10T15")
      (fields
        (field (name "MANUFACTURER") "Yageo")
        (field (name "MANUFACTURER PART NUMBER") "RC0603JR-071ML")
        (field (name "TOLERANCE") "5%")
      )
      (libsource (lib "Altium Content Vault") (part "RES-2"))
    )
    (comp (ref "R118")
      (value "16.5K")
      (footprint "RESC1608X55X30NL15T15")
      (description "RES, 16K5, 1%, 0.1W, 0603, THICK FILM")
      (fields (field (name "MANUFACTURER") "Panasonic") (field (name "PART NUMBER") "ERJ-3EKF1652V"))
      (libsource (lib "Altium Content Vault") (part "RES"))
    )
    (comp (ref "R120")
      (value "10K")
      (footprint "RESC1609X55X30LL15T15")
      (description "Chip Resistor, 10 KOhm, +/- 1%, 0.1 W, -55 to 155 degC, 0603 (1608 Metric), RoHS, Tape and Reel")
      (fields (field (name "TOLERANCE") "1%") (field (name "MANUFACTURER") "Panasonic"))
      (libsource (lib "Altium Content Vault") (part "RES-2"))
    )
    (comp (ref "R182")
      (value "0R")
      (footprint "RESC1608X55X25NL10T15")
      (description "Chip Resistor, 0 Ohm, +/- 5%, 0.1 W, -55 to 155 degC, 0603 (1608 Metric), RoHS, Tape and Reel")
      (fields (field (name "TOLERANCE") "5%") (field (name "MANUFACTURER") "Yageo"))
      (libsource (lib "Altium Content Vault") (part "RES-2"))
    )
    (comp (ref "R208")
      (value "0.47R")
      (footprint "RESC1608X55X25ML10T15")
      (description "Chip Resistor, 0 Ohm, +/- 5%, 0.1 W, -55 to 155 degC, 0603 (1608 Metric), RoHS, Tape and Reel")
      (fields (field (name "TOLERANCE") "5%") (field (name "MANUFACTURER") "Yageo"))
      (libsource (lib "Altium Content Vault") (part "RES-2"))
    )
    (comp (ref "R210")
      (value "49.9R")
      (footprint "RESC1005X40X25NL05T05")
      (fields (field (name "MANUFACTURER") "Panasonic") (field (name "PART NUMBER") "ERJ-2RKF49R9X"))
      (libsource (lib "Altium Content Vault") (part "RES"))
    )
    (comp (ref "R211")
      (value "1K 0.1%")
      (footprint "RESC1608X55X30LL20T20")
      (fields
        (field (name "MANUFACTURER") "Panasonic")
        (field (name "PART NUMBER") "ERA3AEB102V")
        (field (name "MANUFACTURER PART NUMBER") "ERA-3AEB102V")
      )
      (libsource (lib "Altium Content Vault") (part "RES"))
    )
    (comp (ref "R212")
      (value "1.65K 0.1%")
      (footprint "RESC1608X55X30LL20T20")
      (fields
        (field (name "PART NUMBER") "ERA3AEB1651V")
        (field (name "MANUFACTURER") "Panasonic")
        (field (name "MANUFACTURER PART NUMBER") "ERA-3AEB1651V")
      )
      (libsource (lib "Altium Content Vault") (part "RES"))
    )
    (comp (ref "R213")
      (value "180R")
      (footprint "RESC1608X55X25LL10T15")
      (description "Chip Resistor, 180 Ohm, +/- 1%, 0.1 W, -55 to 155 degC, 0603 (1608 Metric), RoHS, Tape and Reel")
      (fields (field (name "TOLERANCE") "1%") (field (name "MANUFACTURER") "Yageo"))
      (libsource (lib "Altium Content Vault") (part "RES-2"))
    )
    (comp (ref "R214")
      (value "59R")
      (footprint "RESC1608X55X30NL15T15")
      (fields
        (field (name "MANUFACTURER") "Panasonic")
        (field (name "PART NUMBER") "ERJ-3EKF59R0V")
        (field (name "TOLERANCE") "1%")
      )
      (libsource (lib "Altium Content Vault") (part "RES"))
    )
    (comp (ref "R215")
      (value "1K")
      (footprint "RESC1608X55X30LL20T10")
      (description "RK73B1JTTD103J")
      (fields (field (name "MANUFACTURER") "KOA Speer") (field (name "TOLERANCE") "5%"))
      (libsource (lib "Altium Content Vault") (part "RES"))
    )
    (comp (ref "R217")
      (value "0R")
      (footprint "RESC1005X40X25NL05T05")
      (fields (field (name "MANUFACTURER") "Panasonic") (field (name "PART NUMBER") "ERJ-2RKF49R9X"))
      (libsource (lib "Altium Content Vault") (part "RES"))
    )
    (comp (ref "U4")
      (value "TS431BILT")
      (footprint "SOT23-5")
      (description "30mA, Low voltage adjustable shunt reference, 1.24 to 6V, 5-Pin SOT23-5, Tape and Reel")
      (libsource (lib "PBL - Integrated Circuits") (part "PM-REF-431-IL5"))
    )
    (comp (ref "U6")
      (value "74AHC1G08SE-7")
      (footprint "DCK0005A_M")
      (description "Single 2-Input Positive-AND Gate, DCK0005A, SMALL T&R")
      (fields
        (field (name "GENERIC PART NUMBER") "SN74AHC1G08")
        (field (name "MANUFACTURER") "Texas Instruments")
      )
      (libsource (lib "Altium Content Vault") (part "TI-SN74XXX1X08-5"))
    )
    (comp (ref "U7")
      (value "1EDN8550B")
      (footprint "SOT23-6")
      (description "Single-channel EiceDRIVER™ with true  differential inputs")
      (libsource (lib "1EDN8550B") (part "1EDN8550B"))
    )
    (comp (ref "U8")
      (value "MCP6V96T")
      (footprint "DCK0005A_N")
      (fields (field (name "PARTNUMBER") "OPA348AIDCKT") (field (name "MANUFACTURER") "Texas Instruments"))
      (libsource (lib "Altium Content Vault") (part "TI-AMP-S3-2-5"))
    )
    (comp (ref "U9")
      (value "TS431BILT")
      (footprint "SOT23-5")
      (description "30mA, Low voltage adjustable shunt reference, 1.24 to 6V, 5-Pin SOT23-5, Tape and Reel")
      (libsource (lib "PBL - Integrated Circuits") (part "PM-REF-431-IL5"))
    )
    (comp (ref "U23")
      (value "STM32G491CCU")
      (footprint "QFN50P700X700X65-49N-D")
      (fields
        (field (name "MANUFACTURER") "STMicroelectronics")
        (field (name "MANUFACTURER PART NUMBER") "STM32G491CCU6")
        (field (name "SUPPLIER PART NUMBER 1") "497-STM32G491CCU6-ND")
      )
      (libsource (lib "SamacSys") (part "STM32G491CCU"))
    )
    (comp (ref "U24")
      (value "TLV9051IDBVR")
      (footprint "SOT23-5")
      (description "2.8 MHz, 150 渭A Op Amp, 5-Pin SOT-23, Extended Temperature Range, Tape and Reel")
      (libsource (lib "PBL - Integrated Circuits") (part "AMP-OPA-MCP601-SOT5"))
    )
    (comp (ref "U25")
      (value "TS431BILT")
      (footprint "SOT23-5")
      (description "30mA, Low voltage adjustable shunt reference, 1.24 to 6V, 5-Pin SOT23-5, Tape and Reel")
      (libsource (lib "PBL - Integrated Circuits") (part "PM-REF-431-IL5"))
    )
  )
  (nets
    (net (code "1") (name "/DAC1") (class "Default")
      (node (ref "C32") (pin "2") (pinfunction "2_2") (pintype "passive"))
      (node (ref "R58") (pin "2") (pinfunction "2_2") (pintype "passive"))
      (node (ref "U23") (pin "13") (pinfunction "PA5_13") (pintype "passive"))
    )
    (net (code "2") (name "/DRV_TOP_HF_MOS") (class "Default")
      (node (ref "CONN_TOP") (pin "1") (pinfunction "1_1") (pintype "passive"))
      (node (ref "R35") (pin "1") (pinfunction "1_1") (pintype "passive"))
      (node (ref "U23") (pin "32") (pinfunction "PA10_32") (pintype "passive"))
    )
    (net (code "3") (name "/EN_DCDC_BOOST") (class "Default")
      (node (ref "IC2") (pin "3") (pinfunction "EN_3") (pintype "passive"))
      (node (ref "R25") (pin "2") (pinfunction "2_2") (pintype "passive"))
    )
    (net (code "4") (name "/HF_TOP_TRIG_ADC") (class "Default")
      (node (ref "CONN_TOP") (pin "5") (pinfunction "5_5") (pintype "passive"))
      (node (ref "U23") (pin "33") (pinfunction "PA11_33") (pintype "passive"))
    )
    (net (code "5") (name "/IAC_ADC2_IN4") (class "Default")
      (node (ref "C164") (pin "2") (pinfunction "2_2") (pintype "passive"))
      (node (ref "C34") (pin "1") (pinfunction "1_1") (pintype "passive"))
      (node (ref "R61") (pin "2") (pinfunction "2_2") (pintype "passive"))
      (node (ref "U23") (pin "15") (pinfunction "PA7_15") (pintype "passive"))
    )
    (net (code "6") (name "/IAC_ADC2_IN5") (class "Default")
      (node (ref "C164") (pin "1") (pinfunction "1_1") (pintype "passive"))
      (node (ref "C165") (pin "2") (pinfunction "2_2") (pintype "passive"))
      (node (ref "R210") (pin "2") (pinfunction "2_2") (pintype "passive"))
      (node (ref "U23") (pin "16") (pinfunction "PC4_16") (pintype "passive"))
    )
    (net (code "7") (name "/IAC_COMP1_INP") (class "Default")
      (node (ref "R182") (pin "2") (pinfunction "2_2") (pintype "passive"))
      (node (ref "R72") (pin "1") (pinfunction "1_1") (pintype "passive"))
      (node (ref "U23") (pin "8") (pinfunction "PA0_8") (pintype "passive"))
      (node (ref "U23") (pin "9") (pinfunction "PA1_9") (pintype "passive"))
    )
    (net (code "9") (name "/IAC_OPAMP2_IN+_COMP4_INP") (class "Default")
      (node (ref "C173") (pin "2") (pinfunction "2_2") (pintype "passive"))
      (node (ref "R44") (pin "2") (pinfunction "2_2") (pintype "passive"))
      (node (ref "U23") (pin "17") (pinfunction "PB0_17") (pintype "passive"))
      (node (ref "U23") (pin "19") (pinfunction "PB2_19") (pintype "passive"))
    )
    (net (code "10") (name "/IAC_OPAMP2_OUT") (class "Default")
      (node (ref "R61") (pin "1") (pinfunction "1_1") (pintype "passive"))
      (node (ref "U23") (pin "14") (pinfunction "PA6_14") (pintype "passive"))
    )
    (net (code "11") (name "/IAC_OPAMP3_OUT") (class "Default")
      (node (ref "R210") (pin "1") (pinfunction "1_1") (pintype "passive"))
      (node (ref "U23") (pin "18") (pinfunction "PB1_18") (pintype "passive"))
    )
    (net (code "12") (name "/IAC_PGA2_VIN+") (class "Default")
      (node (ref "C40") (pin "2") (pinfunction "2_2") (pintype "passive"))
      (node (ref "R217") (pin "2") (pinfunction "2_2") (pintype "passive"))
      (node (ref "R72") (pin "2") (pinfunction "2_2") (pintype "passive"))
      (node (ref "U23") (pin "11") (pinfunction "PA3_11") (pintype "passive"))
    )
    (net (code "13") (name "/IAC_PGA2_VOUT") (class "Default")
      (node (ref "R217") (pin "1") (pinfunction "1_1") (pintype "passive"))
      (node (ref "R44") (pin "1") (pinfunction "1_1") (pintype "passive"))
      (node (ref "U23") (pin "10") (pinfunction "PA2_10") (pintype "passive"))
    )
    (net (code "14") (name "/INV_IND_SHUNT+") (class "Default")
      (node (ref "R63") (pin "1") (pinfunction "1_1") (pintype "passive"))
    )
    (net (code "15") (name "/INV_IND_SHUNT-") (class "Default")
      (node (ref "R73") (pin "1") (pinfunction "1_1") (pintype "passive"))
    )
    (net (code "16") (name "/NCHP_TIM8_CH1") (class "Default")
      (node (ref "R23") (pin "1") (pinfunction "1_1") (pintype "passive"))
      (node (ref "U23") (pin "27") (pinfunction "PB14_27") (pintype "passive"))
    )
    (net (code "17") (name "/NRST") (class "Default")
      (node (ref "C46") (pin "2") (pinfunction "2_2") (pintype "passive"))
      (node (ref "J2") (pin "5") (pinfunction "5_5") (pintype "passive"))
      (node (ref "U23") (pin "7") (pinfunction "PG10-NRST_7") (pintype "passive"))
    )
    (net (code "18") (name "/SPI_MISO_TOP_HF_MOS") (class "Default")
      (node (ref "CONN_TOP") (pin "11") (pinfunction "11_11") (pintype "passive"))
      (node (ref "U23") (pin "42") (pinfunction "PB4_42") (pintype "passive"))
    )
    (net (code "19") (name "/SPI_MOSI_TOP_HF_MOS") (class "Default")
      (node (ref "CONN_TOP") (pin "13") (pinfunction "13_13") (pintype "passive"))
      (node (ref "U23") (pin "43") (pinfunction "PB5_43") (pintype "passive"))
    )
    (net (code "20") (name "/SPI_SCK_TOP_HF_MOS") (class "Default")
      (node (ref "CONN_TOP") (pin "9") (pinfunction "9_9") (pintype "passive"))
      (node (ref "U23") (pin "41") (pinfunction "PB3_41") (pintype "passive"))
    )
    (net (code "21") (name "/STATUS1") (class "Default")
      (node (ref "Q7") (pin "1") (pinfunction "G_1") (pintype "passive"))
      (node (ref "R117") (pin "2") (pinfunction "2_2") (pintype "passive"))
    )
    (net (code "22") (name "/SWCLK") (class "Default")
      (node (ref "J2") (pin "2") (pinfunction "2_2") (pintype "passive"))
      (node (ref "R84") (pin "2") (pinfunction "2_2") (pintype "passive"))
    )
    (net (code "23") (name "/SWDIO") (class "Default")
      (node (ref "J2") (pin "4") (pinfunction "4_4") (pintype "passive"))
      (node (ref "R109") (pin "2") (pinfunction "2_2") (pintype "passive"))
    )
    (net (code "24") (name "/TMON_ADC1_IN2") (class "Default")
      (node (ref "C31") (pin "2") (pinfunction "2_2") (pintype "passive"))
      (node (ref "R54") (pin "2") (pinfunction "2_2") (pintype "passive"))
    )
    (net (code "25") (name "/TMON_NTC") (class "Default")
      (node (ref "C28") (pin "2") (pinfunction "2_2") (pintype "passive"))
      (node (ref "NTC1") (pin "2") (pinfunction "2_2") (pintype "passive"))
      (node (ref "R41") (pin "1") (pinfunction "1_1") (pintype "passive"))
      (node (ref "U23") (pin "6") (pinfunction "PF1-OSC_OUT_6") (pintype "passive"))
    )
    (net (code "26") (name "/TMON_SHUNT_NTC") (class "Default")
      (node (ref "C29") (pin "2") (pinfunction "2_2") (pintype "passive"))
      (node (ref "NTC5") (pin "2") (pinfunction "2_2") (pintype "passive"))
      (node (ref "R42") (pin "1") (pinfunction "1_1") (pintype "passive"))
      (node (ref "U23") (pin "12") (pinfunction "PA4_12") (pintype "passive"))
    )
    (net (code "27") (name "/TOP_HF_TWO_LEVEL_TIM1_CH2") (class "Default")
      (node (ref "R67") (pin "1") (pinfunction "1_1") (pintype "passive"))
      (node (ref "U23") (pin "31") (pinfunction "PA9_31") (pintype "passive"))
    )
    (net (code "28") (name "/TOP_HF_TWO_LEVEL_TIM1_CH2N") (class "Default")
      (node (ref "CONN_TOP") (pin "3") (pinfunction "3_3") (pintype "passive"))
      (node (ref "R34") (pin "1") (pinfunction "1_1") (pintype "passive"))
      (node (ref "U23") (pin "34") (pinfunction "PA12_34") (pintype "passive"))
    )
    (net (code "29") (name "/VDDB_TOP_HF_MOS") (class "Default")
      (node (ref "C174") (pin "2") (pinfunction "2_2") (pintype "passive"))
      (node (ref "D2") (pin "2") (pinfunction "K_2") (pintype "passive"))
      (node (ref "D5") (pin "2") (pinfunction "K_2") (pintype "passive"))
      (node (ref "FB15") (pin "1") (pinfunction "1_1") (pintype "passive"))
    )
    (net (code "30") (name "/VH_TOP_HF_MOS") (class "Default")
      (node (ref "C25") (pin "2") (pinfunction "2_2") (pintype "passive"))
      (node (ref "R17") (pin "2") (pinfunction "2_2") (pintype "passive"))
    )
    (net (code "31") (name "/VL_TOP_HF_MOS") (class "Default")
      (node (ref "R19") (pin "2") (pinfunction "2_2") (pintype "passive"))
    )
    (net (code "32") (name "/VMON_MOS_DRV_N") (class "Default")
      (node (ref "C131") (pin "2") (pinfunction "2_2") (pintype "passive"))
      (node (ref "R55") (pin "1") (pinfunction "1_1") (pintype "passive"))
      (node (ref "R57") (pin "1") (pinfunction "1_1") (pintype "passive"))
      (node (ref "R65") (pin "2") (pinfunction "2_2") (pintype "passive"))
      (node (ref "U23") (pin "25") (pinfunction "PB12_25") (pintype "passive"))
    )
    (net (code "33") (name "/VMON_MOS_DRV_P") (class "Default")
      (node (ref "C63") (pin "2") (pinfunction "2_2") (pintype "passive"))
      (node (ref "R32") (pin "2") (pinfunction "2_2") (pintype "passive"))
      (node (ref "R62") (pin "1") (pinfunction "1_1") (pintype "passive"))
      (node (ref "U23") (pin "24") (pinfunction "PB11_24") (pintype "passive"))
    )
    (net (code "34") (name "Net-(C25-Pad1)") (class "Default")
      (node (ref "C25") (pin "1") (pinfunction "1_1") (pintype "passive"))
      (node (ref "R66") (pin "2") (pinfunction "2_2") (pintype "passive"))
    )
    (net (code "35") (name "Net-(C36-Pad1)") (class "Default")
      (node (ref "C36") (pin "1") (pinfunction "1_1") (pintype "passive"))
      (node (ref "R73") (pin "2") (pinfunction "2_2") (pintype "passive"))
      (node (ref "R75") (pin "1") (pinfunction "1_1") (pintype "passive"))
      (node (ref "R77") (pin "1") (pinfunction "1_1") (pintype "passive"))
    )
    (net (code "36") (name "Net-(C36-Pad2)") (class "Default")
      (node (ref "C36") (pin "2") (pinfunction "2_2") (pintype "passive"))
      (node (ref "R58") (pin "1") (pinfunction "1_1") (pintype "passive"))
      (node (ref "R63") (pin "2") (pinfunction "2_2") (pintype "passive"))
      (node (ref "R64") (pin "1") (pinfunction "1_1") (pintype "passive"))
    )
    (net (code "37") (name "Net-(C133-Pad1)") (class "Default")
      (node (ref "C133") (pin "1") (pinfunction "1_1") (pintype "passive"))
      (node (ref "R1") (pin "2") (pinfunction "2_2") (pintype "passive"))
    )
    (net (code "38") (name "Net-(C159-Pad1)") (class "Default")
      (node (ref "C159") (pin "1") (pinfunction "1_1") (pintype "passive"))
      (node (ref "R208") (pin "2") (pinfunction "2_2") (pintype "passive"))
    )
    (net (code "39") (name "Net-(D1-K{slash}A)") (class "Default")
      (node (ref "C21") (pin "1") (pinfunction "1_1") (pintype "passive"))
      (node (ref "D1") (pin "3") (pinfunction "K/A_3") (pintype "passive"))
    )
    (net (code "40") (name "Net-(D2-A)") (class "Default")
      (node (ref "CONN_TOP") (pin "14") (pinfunction "14_14") (pintype "passive"))
      (node (ref "D2") (pin "1") (pinfunction "A_1") (pintype "passive"))
    )
    (net (code "41") (name "Net-(D5-A)") (class "Default")
      (node (ref "CONN_TOP") (pin "4") (pinfunction "4_4") (pintype "passive"))
      (node (ref "D5") (pin "1") (pinfunction "A_1") (pintype "passive"))
    )
    (net (code "42") (name "Net-(D9-A)") (class "Default")
      (node (ref "C32") (pin "1") (pinfunction "1_1") (pintype "passive"))
      (node (ref "D9") (pin "1") (pinfunction "A_1") (pintype "passive"))
      (node (ref "D9") (pin "2") (pinfunction "K_2") (pintype "passive"))
      (node (ref "R64") (pin "2") (pinfunction "2_2") (pintype "passive"))
      (node (ref "U8") (pin "1") (pinfunction "IN+_1") (pintype "input"))
    )
    (net (code "43") (name "Net-(D9-K{slash}A)") (class "Default")
      (node (ref "C39") (pin "1") (pinfunction "1_1") (pintype "passive"))
      (node (ref "D9") (pin "3") (pinfunction "K/A_3") (pintype "passive"))
      (node (ref "R75") (pin "2") (pinfunction "2_2") (pintype "passive"))
      (node (ref "U8") (pin "3") (pinfunction "IN-_3") (pintype "input"))
    )
    (net (code "44") (name "Net-(D21-K)") (class "Default")
      (node (ref "D21") (pin "1") (pinfunction "K_1") (pintype "passive"))
      (node (ref "R109") (pin "1") (pinfunction "1_1") (pintype "passive"))
      (node (ref "U23") (pin "36") (pinfunction "PA13_36") (pintype "passive"))
    )
    (net (code "45") (name "Net-(D23-K)") (class "Default")
      (node (ref "D23") (pin "1") (pinfunction "K_1") (pintype "passive"))
      (node (ref "R84") (pin "1") (pinfunction "1_1") (pintype "passive"))
      (node (ref "U23") (pin "37") (pinfunction "PA14_37") (pintype "passive"))
    )
    (net (code "46") (name "Net-(IC2-FB)") (class "Default")
      (node (ref "IC2") (pin "6") (pinfunction "FB_6") (pintype "passive"))
      (node (ref "R21") (pin "1") (pinfunction "1_1") (pintype "passive"))
      (node (ref "R24") (pin "2") (pinfunction "2_2") (pintype "passive"))
    )
    (net (code "47") (name "Net-(IC2-OUT)") (class "Default")
      (node (ref "C23") (pin "2") (pinfunction "2_2") (pintype "passive"))
      (node (ref "FB18") (pin "1") (pinfunction "1_1") (pintype "passive"))
      (node (ref "IC2") (pin "1") (pinfunction "OUT_1") (pintype "passive"))
      (node (ref "R21") (pin "2") (pinfunction "2_2") (pintype "passive"))
    )
    (net (code "48") (name "Net-(IC2-SW)") (class "Default")
      (node (ref "IC2") (pin "7") (pinfunction "SW_7") (pintype "passive"))
      (node (ref "L1") (pin "2") (pinfunction "2_2") (pintype "passive"))
    )
    (net (code "49") (name "Net-(LED2-K)") (class "Default")
      (node (ref "LED2") (pin "1") (pinfunction "K_1") (pintype "passive"))
      (node (ref "R114") (pin "2") (pinfunction "2_2") (pintype "passive"))
    )
    (net (code "50") (name "Net-(Q1-D)") (class "Default")
      (node (ref "Q1") (pin "3") (pinfunction "D_3") (pintype "passive"))
      (node (ref "R66") (pin "1") (pinfunction "1_1") (pintype "passive"))
    )
    (net (code "51") (name "Net-(Q1-G)") (class "Default")
      (node (ref "Q1") (pin "1") (pinfunction "G_1") (pintype "passive"))
      (node (ref "R36") (pin "2") (pinfunction "2_2") (pintype "passive"))
      (node (ref "R67") (pin "2") (pinfunction "2_2") (pintype "passive"))
    )
    (net (code "52") (name "Net-(Q2-B)") (class "Default")
      (node (ref "C68") (pin "2") (pinfunction "2_2") (pintype "passive"))
      (node (ref "Q2") (pin "1") (pinfunction "B_1") (pintype "passive"))
      (node (ref "R113") (pin "1") (pinfunction "1_1") (pintype "passive"))
      (node (ref "U9") (pin "3") (pinfunction "K_3") (pintype "passive"))
    )
    (net (code "53") (name "Net-(Q2-E)") (class "Default")
      (node (ref "C71") (pin "2") (pinfunction "2_2") (pintype "passive"))
      (node (ref "FB2") (pin "2") (pinfunction "2_2") (pintype "passive"))
      (node (ref "Q2") (pin "2") (pinfunction "E_2") (pintype "passive"))
      (node (ref "R118") (pin "2") (pinfunction "2_2") (pintype "passive"))
    )
    (net (code "54") (name "Net-(Q4A-B)") (class "Default")
      (node (ref "Q4") (pin "5") (pinfunction "B_5") (pintype "passive"))
      (node (ref "R8") (pin "2") (pinfunction "2_2") (pintype "passive"))
    )
    (net (code "55") (name "Net-(Q4A-C)") (class "Default")
      (node (ref "C21") (pin "2") (pinfunction "2_2") (pintype "passive"))
      (node (ref "Q4") (pin "3") (pinfunction "C_3") (pintype "passive"))
      (node (ref "Q4") (pin "6") (pinfunction "C_6") (pintype "passive"))
    )
    (net (code "56") (name "Net-(Q4A-E)") (class "Default")
      (node (ref "C20") (pin "2") (pinfunction "2_2") (pintype "passive"))
      (node (ref "FB9") (pin "1") (pinfunction "1_1") (pintype "passive"))
      (node (ref "Q4") (pin "4") (pinfunction "E_4") (pintype "passive"))
      (node (ref "R7") (pin "2") (pinfunction "2_2") (pintype "passive"))
    )
    (net (code "57") (name "Net-(Q4B-B)") (class "Default")
      (node (ref "Q4") (pin "2") (pinfunction "B_2") (pintype "passive"))
      (node (ref "R15") (pin "2") (pinfunction "2_2") (pintype "passive"))
    )
    (net (code "58") (name "Net-(Q5-D)") (class "Default")
      (node (ref "Q5") (pin "3") (pinfunction "D_3") (pintype "passive"))
      (node (ref "R15") (pin "1") (pinfunction "1_1") (pintype "passive"))
      (node (ref "R7") (pin "1") (pinfunction "1_1") (pintype "passive"))
      (node (ref "R8") (pin "1") (pinfunction "1_1") (pintype "passive"))
    )
    (net (code "59") (name "Net-(Q5-G)") (class "Default")
      (node (ref "Q5") (pin "1") (pinfunction "G_1") (pintype "passive"))
      (node (ref "R23") (pin "2") (pinfunction "2_2") (pintype "passive"))
      (node (ref "R30") (pin "2") (pinfunction "2_2") (pintype "passive"))
    )
    (net (code "60") (name "Net-(Q6-B)") (class "Default")
      (node (ref "C73") (pin "2") (pinfunction "2_2") (pintype "passive"))
      (node (ref "Q6") (pin "1") (pinfunction "B_1") (pintype "passive"))
      (node (ref "R6") (pin "1") (pinfunction "1_1") (pintype "passive"))
      (node (ref "U4") (pin "3") (pinfunction "K_3") (pintype "passive"))
    )
    (net (code "61") (name "Net-(Q6-E)") (class "Default")
      (node (ref "C101") (pin "2") (pinfunction "2_2") (pintype "passive"))
      (node (ref "FB13") (pin "2") (pinfunction "2_2") (pintype "passive"))
      (node (ref "Q6") (pin "2") (pinfunction "E_2") (pintype "passive"))
      (node (ref "R11") (pin "2") (pinfunction "2_2") (pintype "passive"))
    )
    (net (code "62") (name "Net-(Q7-D)") (class "Default")
      (node (ref "Q7") (pin "3") (pinfunction "D_3") (pintype "passive"))
      (node (ref "R114") (pin "1") (pinfunction "1_1") (pintype "passive"))
    )
    (net (code "63") (name "Net-(U4-REF)") (class "Default")
      (node (ref "C73") (pin "1") (pinfunction "1_1") (pintype "passive"))
      (node (ref "R11") (pin "1") (pinfunction "1_1") (pintype "passive"))
      (node (ref "R33") (pin "2") (pinfunction "2_2") (pintype "passive"))
      (node (ref "U4") (pin "4") (pinfunction "REF_4") (pintype "input"))
    )
    (net (code "64") (name "Net-(U6A-A)") (class "Default")
      (node (ref "C27") (pin "2") (pinfunction "2_2") (pintype "passive"))
      (node (ref "R34") (pin "2") (pinfunction "2_2") (pintype "passive"))
      (node (ref "U6") (pin "1") (pinfunction "A_1") (pintype "input"))
    )
    (net (code "65") (name "Net-(U6A-B)") (class "Default")
      (node (ref "C26") (pin "2") (pinfunction "2_2") (pintype "passive"))
      (node (ref "R35") (pin "2") (pinfunction "2_2") (pintype "passive"))
      (node (ref "U6") (pin "2") (pinfunction "B_2") (pintype "input"))
    )
    (net (code "66") (name "Net-(U6A-Y)") (class "Default")
      (node (ref "R22") (pin "1") (pinfunction "1_1") (pintype "passive"))
      (node (ref "U6") (pin "4") (pinfunction "Y_4") (pintype "output"))
    )
    (net (code "67") (name "Net-(U7-IN+)") (class "Default")
      (node (ref "R22") (pin "2") (pinfunction "2_2") (pintype "passive"))
      (node (ref "U7") (pin "3") (pinfunction "IN+_3") (pintype "passive"))
    )
    (net (code "68") (name "Net-(U7-IN-)") (class "Default")
      (node (ref "R31") (pin "2") (pinfunction "2_2") (pintype "passive"))
      (node (ref "U7") (pin "1") (pinfunction "IN-_1") (pintype "passive"))
    )
    (net (code "69") (name "Net-(U7-OUT_SNK)") (class "Default")
      (node (ref "R19") (pin "1") (pinfunction "1_1") (pintype "passive"))
      (node (ref "U7") (pin "6") (pinfunction "OUT_SNK_6") (pintype "passive"))
    )
    (net (code "70") (name "Net-(U7-OUT_SRC)") (class "Default")
      (node (ref "R17") (pin "1") (pinfunction "1_1") (pintype "passive"))
      (node (ref "U7") (pin "5") (pinfunction "OUT_SRC_5") (pintype "passive"))
    )
    (net (code "71") (name "Net-(U7-VDD)") (class "Default")
      (node (ref "C62") (pin "2") (pinfunction "2_2") (pintype "passive"))
      (node (ref "FB17") (pin "1") (pinfunction "1_1") (pintype "passive"))
      (node (ref "U7") (pin "4") (pinfunction "VDD_4") (pintype "passive"))
    )
    (net (code "72") (name "Net-(U8-OUT)") (class "Default")
      (node (ref "C39") (pin "2") (pinfunction "2_2") (pintype "passive"))
      (node (ref "R182") (pin "1") (pinfunction "1_1") (pintype "passive"))
      (node (ref "R77") (pin "2") (pinfunction "2_2") (pintype "passive"))
      (node (ref "U8") (pin "4") (pinfunction "OUT_4") (pintype "output"))
    )
    (net (code "73") (name "Net-(U9-REF)") (class "Default")
      (node (ref "C68") (pin "1") (pinfunction "1_1") (pintype "passive"))
      (node (ref "R118") (pin "1") (pinfunction "1_1") (pintype "passive"))
      (node (ref "R120") (pin "2") (pinfunction "2_2") (pintype "passive"))
      (node (ref "U9") (pin "4") (pinfunction "REF_4") (pintype "input"))
    )
    (net (code "74") (name "Net-(U23-PB8-BOOT0)") (class "Default")
      (node (ref "R82") (pin "1") (pinfunction "1_1") (pintype "passive"))
      (node (ref "U23") (pin "46") (pinfunction "PB8-BOOT0_46") (pintype "passive"))
    )
    (net (code "75") (name "Net-(U24-VIN+)") (class "Default")
      (node (ref "C170") (pin "2") (pinfunction "2_2") (pintype "passive"))
      (node (ref "R215") (pin "1") (pinfunction "1_1") (pintype "passive"))
      (node (ref "U24") (pin "3") (pinfunction "VIN+_3") (pintype "input"))
    )
    (net (code "76") (name "Net-(U24-VIN-)") (class "Default")
      (node (ref "C168") (pin "1") (pinfunction "1_1") (pintype "passive"))
      (node (ref "R211") (pin "2") (pinfunction "2_2") (pintype "passive"))
      (node (ref "R212") (pin "1") (pinfunction "1_1") (pintype "passive"))
      (node (ref "U24") (pin "4") (pinfunction "VIN-_4") (pintype "input"))
    )
    (net (code "77") (name "Net-(U24-VOUT)") (class "Default")
      (node (ref "C168") (pin "2") (pinfunction "2_2") (pintype "passive"))
      (node (ref "R214") (pin "2") (pinfunction "2_2") (pintype "passive"))
      (node (ref "U24") (pin "1") (pinfunction "VOUT_1") (pintype "output"))
    )
    (net (code "78") (name "Net-(U25-K)") (class "Default")
      (node (ref "R213") (pin "1") (pinfunction "1_1") (pintype "passive"))
      (node (ref "R215") (pin "2") (pinfunction "2_2") (pintype "passive"))
      (node (ref "U25") (pin "3") (pinfunction "K_3") (pintype "passive"))
      (node (ref "U25") (pin "4") (pinfunction "REF_4") (pintype "input"))
    )
    (net (code "79") (name "TOP_HF_GND") (class "Default")
      (node (ref "C100") (pin "1") (pinfunction "1_1") (pintype "passive"))
      (node (ref "C101") (pin "1") (pinfunction "1_1") (pintype "passive"))
      (node (ref "C11") (pin "1") (pinfunction "1_1") (pintype "passive"))
      (node (ref "C12") (pin "1") (pinfunction "1_1") (pintype "passive"))
      (node (ref "C13") (pin "2") (pinfunction "2_2") (pintype "passive"))
      (node (ref "C131") (pin "1") (pinfunction "1_1") (pintype "passive"))
      (node (ref "C139") (pin "1") (pinfunction "1_1") (pintype "passive"))
      (node (ref "C14") (pin "2") (pinfunction "2_2") (pintype "passive"))
      (node (ref "C140") (pin "1") (pinfunction "1_1") (pintype "passive"))
      (node (ref "C15") (pin "2") (pinfunction "2_2") (pintype "passive"))
      (node (ref "C157") (pin "1") (pinfunction "1_1") (pintype "passive"))
      (node (ref "C165") (pin "1") (pinfunction "1_1") (pintype "passive"))
      (node (ref "C166") (pin "2") (pinfunction "2_2") (pintype "passive"))
      (node (ref "C167") (pin "2") (pinfunction "2_2") (pintype "passive"))
      (node (ref "C169") (pin "1") (pinfunction "1_1") (pintype "passive"))
      (node (ref "C170") (pin "1") (pinfunction "1_1") (pintype "passive"))
      (node (ref "C171") (pin "1") (pinfunction "1_1") (pintype "passive"))
      (node (ref "C172") (pin "1") (pinfunction "1_1") (pintype "passive"))
      (node (ref "C173") (pin "1") (pinfunction "1_1") (pintype "passive"))
      (node (ref "C174") (pin "1") (pinfunction "1_1") (pintype "passive"))
      (node (ref "C20") (pin "1") (pinfunction "1_1") (pintype "passive"))
      (node (ref "C22") (pin "1") (pinfunction "1_1") (pintype "passive"))
      (node (ref "C23") (pin "1") (pinfunction "1_1") (pintype "passive"))
      (node (ref "C24") (pin "1") (pinfunction "1_1") (pintype "passive"))
      (node (ref "C26") (pin "1") (pinfunction "1_1") (pintype "passive"))
      (node (ref "C27") (pin "1") (pinfunction "1_1") (pintype "passive"))
      (node (ref "C28") (pin "1") (pinfunction "1_1") (pintype "passive"))
      (node (ref "C29") (pin "1") (pinfunction "1_1") (pintype "passive"))
      (node (ref "C31") (pin "1") (pinfunction "1_1") (pintype "passive"))
      (node (ref "C34") (pin "2") (pinfunction "2_2") (pintype "passive"))
      (node (ref "C40") (pin "1") (pinfunction "1_1") (pintype "passive"))
      (node (ref "C44") (pin "2") (pinfunction "2_2") (pintype "passive"))
      (node (ref "C46") (pin "1") (pinfunction "1_1") (pintype "passive"))
      (node (ref "C63") (pin "1") (pinfunction "1_1") (pintype "passive"))
      (node (ref "C64") (pin "1") (pinfunction "1_1") (pintype "passive"))
      (node (ref "C69") (pin "1") (pinfunction "1_1") (pintype "passive"))
      (node (ref "C7") (pin "1") (pinfunction "1_1") (pintype "passive"))
      (node (ref "C70") (pin "1") (pinfunction "1_1") (pintype "passive"))
      (node (ref "C71") (pin "1") (pinfunction "1_1") (pintype "passive"))
      (node (ref "C9") (pin "1") (pinfunction "1_1") (pintype "passive"))
      (node (ref "CONN_TOP") (pin "10") (pinfunction "10_10") (pintype "passive"))
      (node (ref "CONN_TOP") (pin "12") (pinfunction "12_12") (pintype "passive"))
      (node (ref "CONN_TOP") (pin "15") (pinfunction "15_15") (pintype "passive"))
      (node (ref "CONN_TOP") (pin "16") (pinfunction "16_16") (pintype "passive"))
      (node (ref "CONN_TOP") (pin "2") (pinfunction "2_2") (pintype "passive"))
      (node (ref "CONN_TOP") (pin "6") (pinfunction "6_6") (pintype "passive"))
      (node (ref "CONN_TOP") (pin "7") (pinfunction "7_7") (pintype "passive"))
      (node (ref "CONN_TOP") (pin "8") (pinfunction "8_8") (pintype "passive"))
      (node (ref "D1") (pin "2") (pinfunction "K_2") (pintype "passive"))
      (node (ref "D21") (pin "2") (pinfunction "A_2") (pintype "passive"))
      (node (ref "D23") (pin "2") (pinfunction "A_2") (pintype "passive"))
      (node (ref "IC2") (pin "4") (pinfunction "AGND_4") (pintype "passive"))
      (node (ref "IC2") (pin "5") (pinfunction "NC_5") (pintype "passive"))
      (node (ref "IC2") (pin "8") (pinfunction "PGND_8") (pintype "passive"))
      (node (ref "IC2") (pin "9") (pinfunction "EP_9") (pintype "passive"))
      (node (ref "J2") (pin "3") (pinfunction "3_3") (pintype "passive"))
      (node (ref "J2") (pin "6") (pinfunction "6_6") (pintype "passive"))
      (node (ref "NTC1") (pin "1") (pinfunction "1_1") (pintype "passive"))
      (node (ref "NTC5") (pin "1") (pinfunction "1_1") (pintype "passive"))
      (node (ref "Q1") (pin "2") (pinfunction "S_2") (pintype "passive"))
      (node (ref "Q4") (pin "1") (pinfunction "E_1") (pintype "passive"))
      (node (ref "Q5") (pin "2") (pinfunction "S_2") (pintype "passive"))
      (node (ref "Q7") (pin "2") (pinfunction "S_2") (pintype "passive"))
      (node (ref "R1") (pin "1") (pinfunction "1_1") (pintype "passive"))
      (node (ref "R117") (pin "1") (pinfunction "1_1") (pintype "passive"))
      (node (ref "R120") (pin "1") (pinfunction "1_1") (pintype "passive"))
      (node (ref "R208") (pin "1") (pinfunction "1_1") (pintype "passive"))
      (node (ref "R212") (pin "2") (pinfunction "2_2") (pintype "passive"))
      (node (ref "R24") (pin "1") (pinfunction "1_1") (pintype "passive"))
      (node (ref "R25") (pin "1") (pinfunction "1_1") (pintype "passive"))
      (node (ref "R30") (pin "1") (pinfunction "1_1") (pintype "passive"))
      (node (ref "R31") (pin "1") (pinfunction "1_1") (pintype "passive"))
      (node (ref "R33") (pin "1") (pinfunction "1_1") (pintype "passive"))
      (node (ref "R36") (pin "1") (pinfunction "1_1") (pintype "passive"))
      (node (ref "R62") (pin "2") (pinfunction "2_2") (pintype "passive"))
      (node (ref "R65") (pin "1") (pinfunction "1_1") (pintype "passive"))
      (node (ref "R82") (pin "2") (pinfunction "2_2") (pintype "passive"))
      (node (ref "U23") (pin "49") (pinfunction "VSS_49") (pintype "passive"))
      (node (ref "U24") (pin "2") (pinfunction "VSS_2") (pintype "power_in"))
      (node (ref "U25") (pin "5") (pinfunction "A_5") (pintype "passive"))
      (node (ref "U4") (pin "5") (pinfunction "A_5") (pintype "passive"))
      (node (ref "U6") (pin "3") (pinfunction "GND_3") (pintype "power_in"))
      (node (ref "U8") (pin "2") (pinfunction "V-_2") (pintype "power_in"))
      (node (ref "U9") (pin "5") (pinfunction "A_5") (pintype "passive"))
    )
    (net (code "80") (name "TOP_HF_VREF") (class "Default")
      (node (ref "C169") (pin "2") (pinfunction "2_2") (pintype "passive"))
      (node (ref "R211") (pin "1") (pinfunction "1_1") (pintype "passive"))
      (node (ref "R214") (pin "1") (pinfunction "1_1") (pintype "passive"))
      (node (ref "U23") (pin "20") (pinfunction "VREF+_20") (pintype "passive"))
    )
    (net (code "81") (name "TOP_HF_V_3V3A") (class "Default")
      (node (ref "C139") (pin "2") (pinfunction "2_2") (pintype "passive"))
      (node (ref "C171") (pin "2") (pinfunction "2_2") (pintype "passive"))
      (node (ref "C172") (pin "2") (pinfunction "2_2") (pintype "passive"))
      (node (ref "C69") (pin "2") (pinfunction "2_2") (pintype "passive"))
      (node (ref "FB2") (pin "1") (pinfunction "1_1") (pintype "passive"))
      (node (ref "R213") (pin "2") (pinfunction "2_2") (pintype "passive"))
      (node (ref "R41") (pin "2") (pinfunction "2_2") (pintype "passive"))
      (node (ref "R42") (pin "2") (pinfunction "2_2") (pintype "passive"))
      (node (ref "U23") (pin "21") (pinfunction "VDDA_21") (pintype "passive"))
      (node (ref "U24") (pin "5") (pinfunction "VDD_5") (pintype "power_in"))
      (node (ref "U8") (pin "5") (pinfunction "V+_5") (pintype "power_in"))
    )
    (net (code "82") (name "TOP_HF_V_3V3D") (class "Default")
      (node (ref "C100") (pin "2") (pinfunction "2_2") (pintype "passive"))
      (node (ref "C140") (pin "2") (pinfunction "2_2") (pintype "passive"))
      (node (ref "C166") (pin "1") (pinfunction "1_1") (pintype "passive"))
      (node (ref "C167") (pin "1") (pinfunction "1_1") (pintype "passive"))
      (node (ref "C44") (pin "1") (pinfunction "1_1") (pintype "passive"))
      (node (ref "C64") (pin "2") (pinfunction "2_2") (pintype "passive"))
      (node (ref "FB13") (pin "1") (pinfunction "1_1") (pintype "passive"))
      (node (ref "J2") (pin "1") (pinfunction "1_1") (pintype "passive"))
      (node (ref "LED2") (pin "2") (pinfunction "A_2") (pintype "passive"))
      (node (ref "U23") (pin "1") (pinfunction "VBAT_1") (pintype "passive"))
      (node (ref "U23") (pin "23") (pinfunction "VDD_1_23") (pintype "passive"))
      (node (ref "U23") (pin "35") (pinfunction "VDD_2_35") (pintype "passive"))
      (node (ref "U23") (pin "48") (pinfunction "VDD_3_48") (pintype "passive"))
      (node (ref "U6") (pin "5") (pinfunction "VCC_5") (pintype "power_in"))
    )
    (net (code "83") (name "TOP_HF_V_3VN") (class "Default")
      (node (ref "C13") (pin "1") (pinfunction "1_1") (pintype "passive"))
      (node (ref "C14") (pin "1") (pinfunction "1_1") (pintype "passive"))
      (node (ref "C15") (pin "1") (pinfunction "1_1") (pintype "passive"))
      (node (ref "C24") (pin "2") (pinfunction "2_2") (pintype "passive"))
      (node (ref "C62") (pin "1") (pinfunction "1_1") (pintype "passive"))
      (node (ref "D1") (pin "1") (pinfunction "A_1") (pintype "passive"))
      (node (ref "R55") (pin "2") (pinfunction "2_2") (pintype "passive"))
      (node (ref "U7") (pin "2") (pinfunction "GND_2") (pintype "passive"))
    )
    (net (code "84") (name "TOP_HF_V_5VP") (class "Default")
      (node (ref "C12") (pin "2") (pinfunction "2_2") (pintype "passive"))
      (node (ref "C133") (pin "2") (pinfunction "2_2") (pintype "passive"))
      (node (ref "C157") (pin "2") (pinfunction "2_2") (pintype "passive"))
      (node (ref "C22") (pin "2") (pinfunction "2_2") (pintype "passive"))
      (node (ref "C70") (pin "2") (pinfunction "2_2") (pintype "passive"))
      (node (ref "FB15") (pin "2") (pinfunction "2_2") (pintype "passive"))
      (node (ref "FB9") (pin "2") (pinfunction "2_2") (pintype "passive"))
      (node (ref "IC2") (pin "2") (pinfunction "VIN_2") (pintype "passive"))
      (node (ref "L1") (pin "1") (pinfunction "1_1") (pintype "passive"))
      (node (ref "Q2") (pin "3") (pinfunction "C_3") (pintype "passive"))
      (node (ref "Q6") (pin "3") (pinfunction "C_3") (pintype "passive"))
      (node (ref "R113") (pin "2") (pinfunction "2_2") (pintype "passive"))
      (node (ref "R57") (pin "2") (pinfunction "2_2") (pintype "passive"))
      (node (ref "R6") (pin "2") (pinfunction "2_2") (pintype "passive"))
    )
    (net (code "85") (name "TOP_HF_V_16VP") (class "Default")
      (node (ref "C11") (pin "2") (pinfunction "2_2") (pintype "passive"))
      (node (ref "C159") (pin "2") (pinfunction "2_2") (pintype "passive"))
      (node (ref "C7") (pin "2") (pinfunction "2_2") (pintype "passive"))
      (node (ref "C9") (pin "2") (pinfunction "2_2") (pintype "passive"))
      (node (ref "FB17") (pin "2") (pinfunction "2_2") (pintype "passive"))
      (node (ref "FB18") (pin "2") (pinfunction "2_2") (pintype "passive"))
      (node (ref "R32") (pin "1") (pinfunction "1_1") (pintype "passive"))
    )
    (net (code "86") (name "unconnected-(R54-Pad1)") (class "Default")
      (node (ref "R54") (pin "1") (pinfunction "1_1") (pintype "passive"))
    )
    (net (code "87") (name "unconnected-(U4-NC-Pad1)") (class "Default")
      (node (ref "U4") (pin "1") (pinfunction "NC_1") (pintype "passive"))
    )
    (net (code "88") (name "unconnected-(U4-NC-Pad2)") (class "Default")
      (node (ref "U4") (pin "2") (pinfunction "NC_2") (pintype "passive"))
    )
    (net (code "89") (name "unconnected-(U9-NC-Pad1)") (class "Default")
      (node (ref "U9") (pin "1") (pinfunction "NC_1") (pintype "passive"))
    )
    (net (code "90") (name "unconnected-(U9-NC-Pad2)") (class "Default")
      (node (ref "U9") (pin "2") (pinfunction "NC_2") (pintype "passive"))
    )
    (net (code "91") (name "unconnected-(U23-PA8-Pad30)") (class "Default")
      (node (ref "U23") (pin "30") (pinfunction "PA8_30") (pintype "passive"))
    )
    (net (code "92") (name "unconnected-(U23-PA15-Pad38)") (class "Default")
      (node (ref "U23") (pin "38") (pinfunction "PA15_38") (pintype "passive"))
    )
    (net (code "93") (name "unconnected-(U23-PB6-Pad44)") (class "Default")
      (node (ref "U23") (pin "44") (pinfunction "PB6_44") (pintype "passive"))
    )
    (net (code "94") (name "unconnected-(U23-PB7-Pad45)") (class "Default")
      (node (ref "U23") (pin "45") (pinfunction "PB7_45") (pintype "passive"))
    )
    (net (code "95") (name "unconnected-(U23-PB9-Pad47)") (class "Default")
      (node (ref "U23") (pin "47") (pinfunction "PB9_47") (pintype "passive"))
    )
    (net (code "96") (name "unconnected-(U23-PB10-Pad22)") (class "Default")
      (node (ref "U23") (pin "22") (pinfunction "PB10_22") (pintype "passive"))
    )
    (net (code "97") (name "unconnected-(U23-PB13-Pad26)") (class "Default")
      (node (ref "U23") (pin "26") (pinfunction "PB13_26") (pintype "passive"))
    )
    (net (code "98") (name "unconnected-(U23-PB15-Pad28)") (class "Default")
      (node (ref "U23") (pin "28") (pinfunction "PB15_28") (pintype "passive"))
    )
    (net (code "99") (name "unconnected-(U23-PC6-Pad29)") (class "Default")
      (node (ref "U23") (pin "29") (pinfunction "PC6_29") (pintype "passive"))
    )
    (net (code "100") (name "unconnected-(U23-PC10-Pad39)") (class "Default")
      (node (ref "U23") (pin "39") (pinfunction "PC10_39") (pintype "passive"))
    )
    (net (code "101") (name "unconnected-(U23-PC11-Pad40)") (class "Default")
      (node (ref "U23") (pin "40") (pinfunction "PC11_40") (pintype "passive"))
    )
    (net (code "102") (name "unconnected-(U23-PC13-Pad2)") (class "Default")
      (node (ref "U23") (pin "2") (pinfunction "PC13_2") (pintype "passive"))
    )
    (net (code "103") (name "unconnected-(U23-PC14-OSC32_IN-Pad3)") (class "Default")
      (node (ref "U23") (pin "3") (pinfunction "PC14-OSC32_IN_3") (pintype "passive"))
    )
    (net (code "104") (name "unconnected-(U23-PC15-OSC32_OUT-Pad4)") (class "Default")
      (node (ref "U23") (pin "4") (pinfunction "PC15-OSC32_OUT_4") (pintype "passive"))
    )
    (net (code "105") (name "unconnected-(U23-PF0-OSC_IN-Pad5)") (class "Default")
      (node (ref "U23") (pin "5") (pinfunction "PF0-OSC_IN_5") (pintype "passive"))
    )
    (net (code "106") (name "unconnected-(U25-NC-Pad1)") (class "Default")
      (node (ref "U25") (pin "1") (pinfunction "NC_1") (pintype "passive"))
    )
    (net (code "107") (name "unconnected-(U25-NC-Pad2)") (class "Default")
      (node (ref "U25") (pin "2") (pinfunction "NC_2") (pintype "passive"))
    )
  )
)
